# 12.net
KiCad netlist of a schematic drawn in Altium Designer
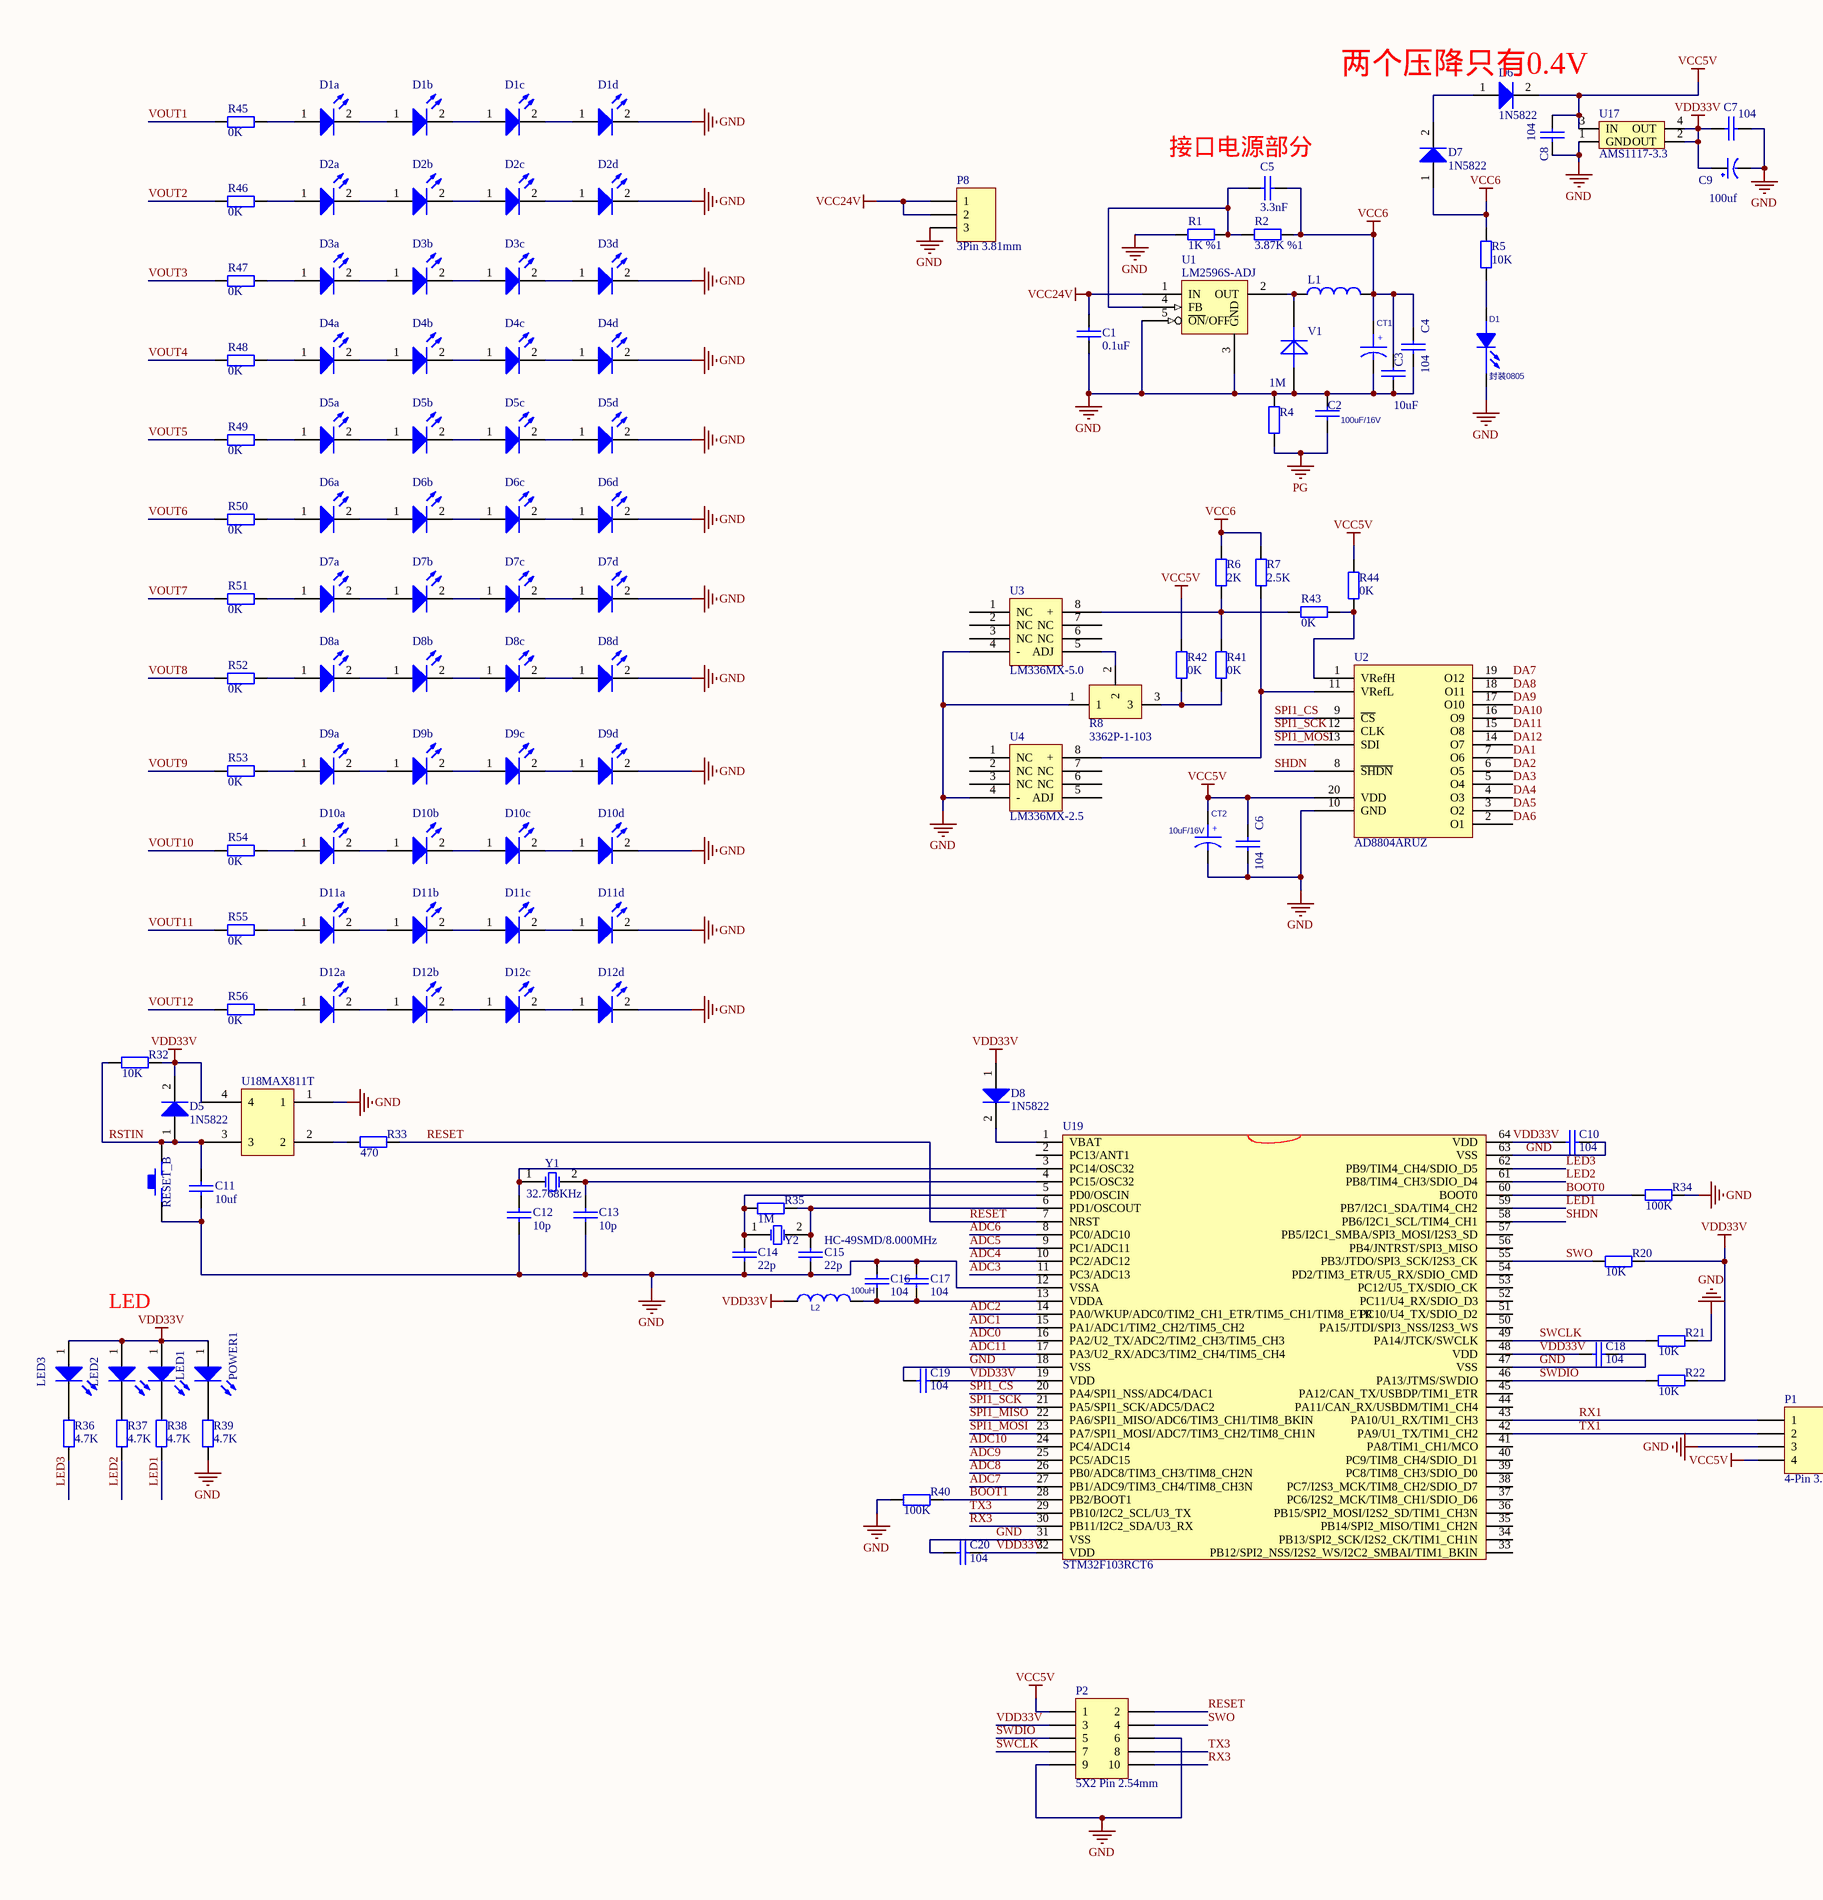
[diagram p0: 数粒机发射板12通道.SchDoc, left]
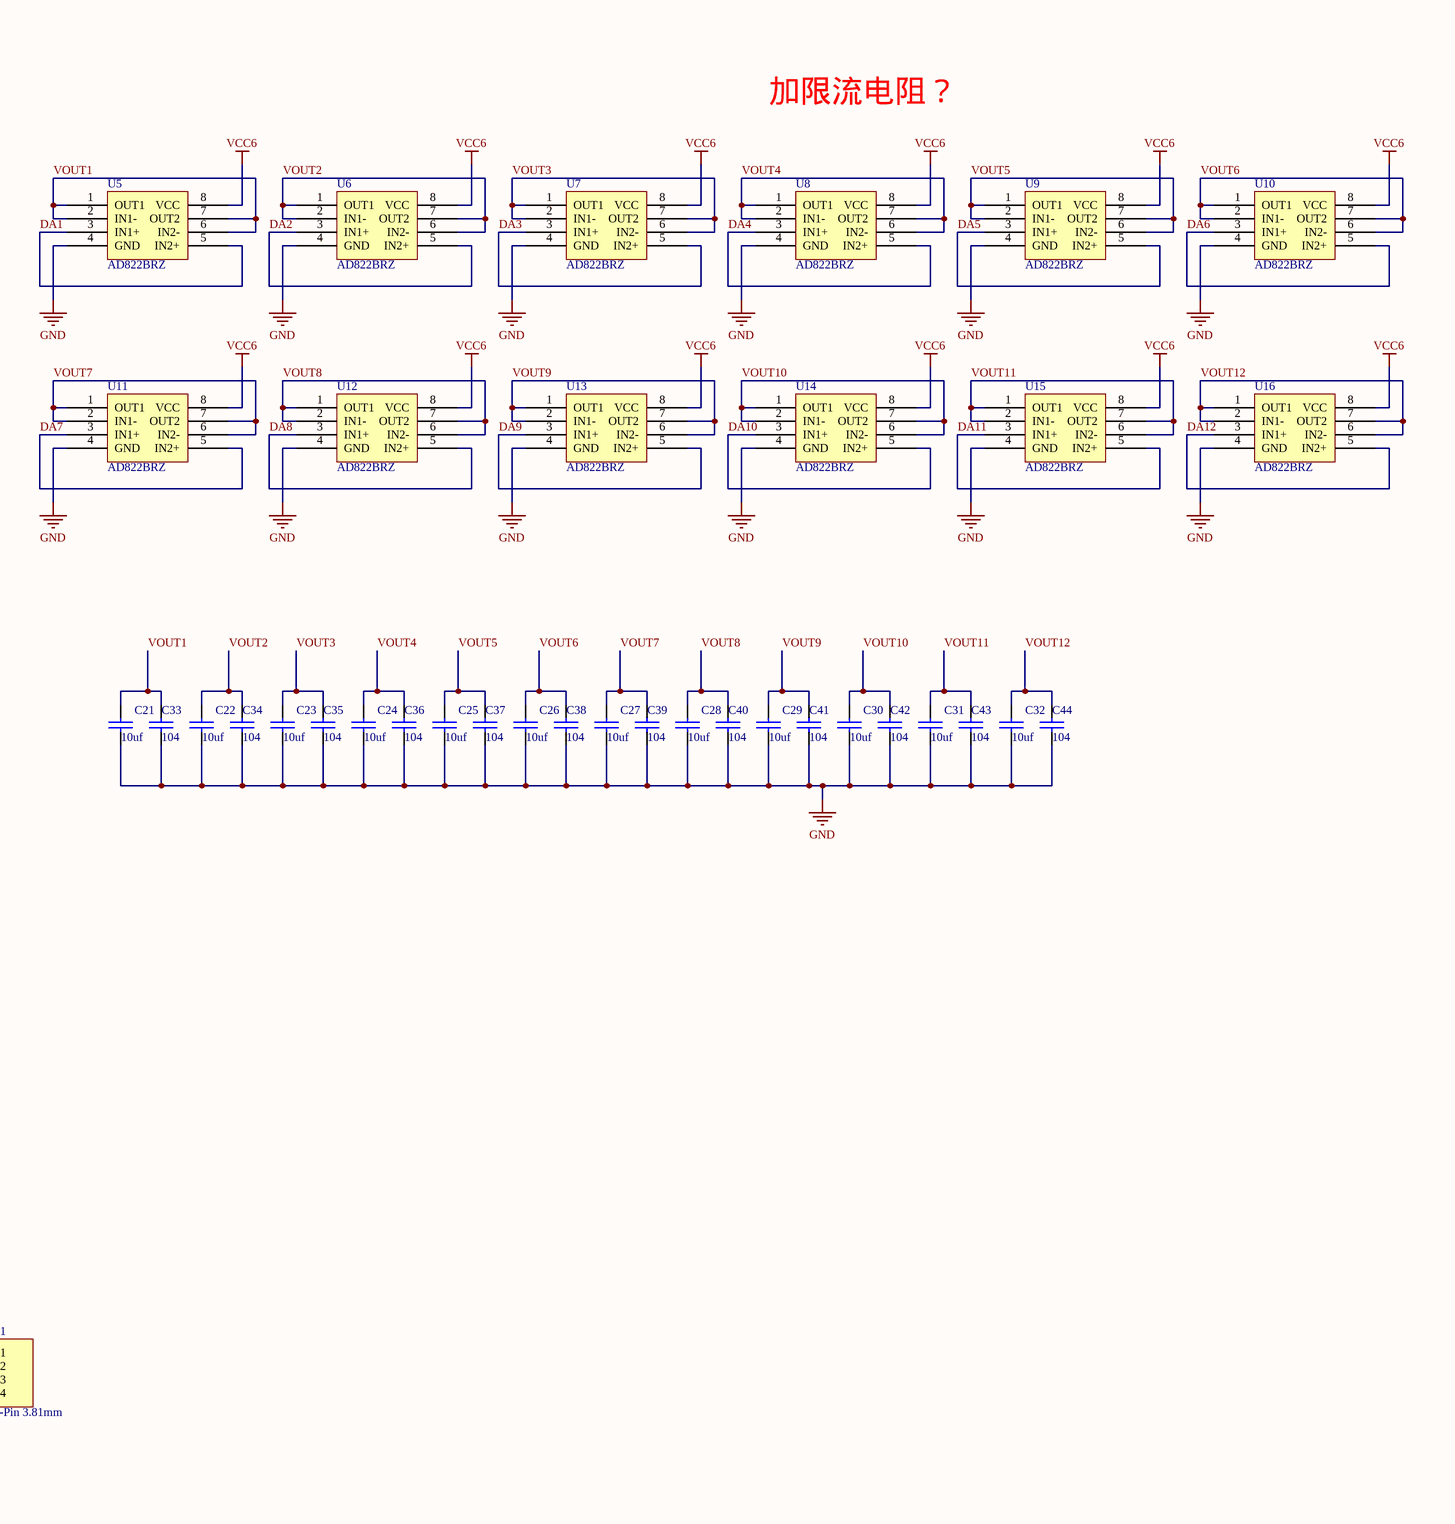
[diagram p1: 数粒机发射板12通道.SchDoc, right]

(export (version "E")
  (design (tool "Eeschema 10.0.6"))
  (components
    (comp (ref "C1")
      (value "0.1uF")
      (footprint "0805C")
      (description "贴片电容")
      (libsource (lib "*") (part "Pro92D1.TMP_105_9"))
    )
    (comp (ref "C2")
      (value "102/2KV")
      (footprint "0805CC")
      (description "贴片电容")
      (libsource (lib "*") (part "CAP"))
    )
    (comp (ref "C3")
      (value "10uF")
      (footprint "0805C")
      (description "贴片电容")
      (libsource (lib "*") (part "Pro92D1.TMP_105_9"))
    )
    (comp (ref "C4")
      (value "104")
      (footprint "0805C")
      (description "贴片电容")
      (libsource (lib "*") (part "CAP"))
    )
    (comp (ref "C5")
      (value "3.3nF")
      (footprint "0805C")
      (description "贴片电容")
      (libsource (lib "*") (part "CAP"))
    )
    (comp (ref "C6")
      (value "104")
      (footprint "0805C")
      (description "贴片电容")
      (libsource (lib "*") (part "CAP"))
    )
    (comp (ref "C7")
      (value "104")
      (footprint "0805C")
      (description "贴片电容")
      (libsource (lib "*") (part "CAP"))
    )
    (comp (ref "C8")
      (value "104")
      (footprint "0805C")
      (description "贴片电容")
      (libsource (lib "*") (part "CAP"))
    )
    (comp (ref "C9")
      (value "100uf")
      (footprint "CC6.56.5")
      (description "贴片电解电容")
      (fields (field (name "Comment") "10SEV100M6.3X5.5"))
      (libsource (lib "WarShip V3 STM32103封装库") (part "CAP"))
    )
    (comp (ref "C10")
      (value "104")
      (footprint "0805C")
      (description "贴片电容")
      (libsource (lib "*") (part "CAP"))
    )
    (comp (ref "C11")
      (value "10uf")
      (footprint "0805C")
      (description "贴片电容")
      (libsource (lib "*") (part "CAP"))
    )
    (comp (ref "C12")
      (value "10p")
      (footprint "0805C")
      (description "贴片电容")
      (libsource (lib "*") (part "CAP"))
    )
    (comp (ref "C13")
      (value "10p")
      (footprint "0805C")
      (description "贴片电容")
      (libsource (lib "*") (part "CAP"))
    )
    (comp (ref "C14")
      (value "22p")
      (footprint "0805C")
      (description "贴片电容")
      (libsource (lib "*") (part "CAP"))
    )
    (comp (ref "C15")
      (value "22p")
      (footprint "0805C")
      (description "贴片电容")
      (libsource (lib "*") (part "CAP"))
    )
    (comp (ref "C16")
      (value "104")
      (footprint "0805C")
      (description "贴片电容")
      (libsource (lib "*") (part "CAP"))
    )
    (comp (ref "C17")
      (value "104")
      (footprint "0805C")
      (description "贴片电容")
      (libsource (lib "*") (part "CAP"))
    )
    (comp (ref "C18")
      (value "104")
      (footprint "0805C")
      (description "贴片电容")
      (libsource (lib "*") (part "CAP"))
    )
    (comp (ref "C19")
      (value "104")
      (footprint "0805C")
      (description "贴片电容")
      (libsource (lib "*") (part "CAP"))
    )
    (comp (ref "C20")
      (value "104")
      (footprint "0805C")
      (description "贴片电容")
      (libsource (lib "*") (part "CAP"))
    )
    (comp (ref "C21")
      (value "10uf")
      (footprint "0805C")
      (description "贴片电容")
      (libsource (lib "*") (part "CAP"))
    )
    (comp (ref "C22")
      (value "10uf")
      (footprint "0805C")
      (description "贴片电容")
      (libsource (lib "*") (part "CAP"))
    )
    (comp (ref "C23")
      (value "10uf")
      (footprint "0805C")
      (description "贴片电容")
      (libsource (lib "*") (part "CAP"))
    )
    (comp (ref "C24")
      (value "10uf")
      (footprint "0805C")
      (description "贴片电容")
      (libsource (lib "*") (part "CAP"))
    )
    (comp (ref "C25")
      (value "10uf")
      (footprint "0805C")
      (description "贴片电容")
      (libsource (lib "*") (part "CAP"))
    )
    (comp (ref "C26")
      (value "10uf")
      (footprint "0805C")
      (description "贴片电容")
      (libsource (lib "*") (part "CAP"))
    )
    (comp (ref "C27")
      (value "10uf")
      (footprint "0805C")
      (description "贴片电容")
      (libsource (lib "*") (part "CAP"))
    )
    (comp (ref "C28")
      (value "10uf")
      (footprint "0805C")
      (description "贴片电容")
      (libsource (lib "*") (part "CAP"))
    )
    (comp (ref "C29")
      (value "10uf")
      (footprint "0805C")
      (description "贴片电容")
      (libsource (lib "*") (part "CAP"))
    )
    (comp (ref "C30")
      (value "10uf")
      (footprint "0805C")
      (description "贴片电容")
      (libsource (lib "*") (part "CAP"))
    )
    (comp (ref "C31")
      (value "10uf")
      (footprint "0805C")
      (description "贴片电容")
      (libsource (lib "*") (part "CAP"))
    )
    (comp (ref "C32")
      (value "10uf")
      (footprint "0805C")
      (description "贴片电容")
      (libsource (lib "*") (part "CAP"))
    )
    (comp (ref "C33")
      (value "104")
      (footprint "0805C")
      (description "贴片电容")
      (libsource (lib "*") (part "CAP"))
    )
    (comp (ref "C34")
      (value "104")
      (footprint "0805C")
      (description "贴片电容")
      (libsource (lib "*") (part "CAP"))
    )
    (comp (ref "C35")
      (value "104")
      (footprint "0805C")
      (description "贴片电容")
      (libsource (lib "*") (part "CAP"))
    )
    (comp (ref "C36")
      (value "104")
      (footprint "0805C")
      (description "贴片电容")
      (libsource (lib "*") (part "CAP"))
    )
    (comp (ref "C37")
      (value "104")
      (footprint "0805C")
      (description "贴片电容")
      (libsource (lib "*") (part "CAP"))
    )
    (comp (ref "C38")
      (value "104")
      (footprint "0805C")
      (description "贴片电容")
      (libsource (lib "*") (part "CAP"))
    )
    (comp (ref "C39")
      (value "104")
      (footprint "0805C")
      (description "贴片电容")
      (libsource (lib "*") (part "CAP"))
    )
    (comp (ref "C40")
      (value "104")
      (footprint "0805C")
      (description "贴片电容")
      (libsource (lib "*") (part "CAP"))
    )
    (comp (ref "C41")
      (value "104")
      (footprint "0805C")
      (description "贴片电容")
      (libsource (lib "*") (part "CAP"))
    )
    (comp (ref "C42")
      (value "104")
      (footprint "0805C")
      (description "贴片电容")
      (libsource (lib "*") (part "CAP"))
    )
    (comp (ref "C43")
      (value "104")
      (footprint "0805C")
      (description "贴片电容")
      (libsource (lib "*") (part "CAP"))
    )
    (comp (ref "C44")
      (value "104")
      (footprint "0805C")
      (description "贴片电容")
      (libsource (lib "*") (part "CAP"))
    )
    (comp (ref "CT1")
      (value "100uF/16V")
      (description "钽电容")
      (fields (field (name "VENDOR PART#") "495-2256-1-ND") (field (name "MFG PART#") "B45196H3107M409"))
      (libsource (lib "*") (part "CAP POL"))
    )
    (comp (ref "CT2")
      (value "10uF/16V")
      (description "钽电容")
      (fields (field (name "VENDOR PART#") "495-2256-1-ND") (field (name "MFG PART#") "B45196H3107M409"))
      (libsource (lib "*") (part "CAP POL"))
    )
    (comp (ref "D1")
      (value "封装0805")
      (description "二极管(贴片发光红色)")
      (fields (field (name "VENDOR PART#") "160-1426-1-ND") (field (name "MFG PART#") "LTST-C171KGKT"))
      (libsource (lib "*") (part "LED"))
    )
    (comp (ref "D1a")
      (value "EL-1KL3")
      (footprint "EL-1KL3")
      (description "红外接收珠子")
      (fields (field (name "PUBLISHER") "Altium Limited"))
      (libsource (lib "Miscellaneous Devices") (part "EL-1KL3"))
    )
    (comp (ref "D1b")
      (value "EL-1KL3")
      (footprint "EL-1KL3")
      (description "红外接收珠子")
      (fields (field (name "PUBLISHER") "Altium Limited"))
      (libsource (lib "Miscellaneous Devices") (part "EL-1KL3"))
    )
    (comp (ref "D1c")
      (value "EL-1KL3")
      (footprint "EL-1KL3")
      (description "红外接收珠子")
      (fields (field (name "PUBLISHER") "Altium Limited"))
      (libsource (lib "Miscellaneous Devices") (part "EL-1KL3"))
    )
    (comp (ref "D1d")
      (value "EL-1KL3")
      (footprint "EL-1KL3")
      (description "红外接收珠子")
      (fields (field (name "PUBLISHER") "Altium Limited"))
      (libsource (lib "Miscellaneous Devices") (part "EL-1KL3"))
    )
    (comp (ref "D2a")
      (value "EL-1KL3")
      (footprint "EL-1KL3")
      (description "红外接收珠子")
      (fields (field (name "PUBLISHER") "Altium Limited"))
      (libsource (lib "Miscellaneous Devices") (part "EL-1KL3"))
    )
    (comp (ref "D2b")
      (value "EL-1KL3")
      (footprint "EL-1KL3")
      (description "红外接收珠子")
      (fields (field (name "PUBLISHER") "Altium Limited"))
      (libsource (lib "Miscellaneous Devices") (part "EL-1KL3"))
    )
    (comp (ref "D2c")
      (value "EL-1KL3")
      (footprint "EL-1KL3")
      (description "红外接收珠子")
      (fields (field (name "PUBLISHER") "Altium Limited"))
      (libsource (lib "Miscellaneous Devices") (part "EL-1KL3"))
    )
    (comp (ref "D2d")
      (value "EL-1KL3")
      (footprint "EL-1KL3")
      (description "红外接收珠子")
      (fields (field (name "PUBLISHER") "Altium Limited"))
      (libsource (lib "Miscellaneous Devices") (part "EL-1KL3"))
    )
    (comp (ref "D3a")
      (value "EL-1KL3")
      (footprint "EL-1KL3")
      (description "红外接收珠子")
      (fields (field (name "PUBLISHER") "Altium Limited"))
      (libsource (lib "Miscellaneous Devices") (part "EL-1KL3"))
    )
    (comp (ref "D3b")
      (value "EL-1KL3")
      (footprint "EL-1KL3")
      (description "红外接收珠子")
      (fields (field (name "PUBLISHER") "Altium Limited"))
      (libsource (lib "Miscellaneous Devices") (part "EL-1KL3"))
    )
    (comp (ref "D3c")
      (value "EL-1KL3")
      (footprint "EL-1KL3")
      (description "红外接收珠子")
      (fields (field (name "PUBLISHER") "Altium Limited"))
      (libsource (lib "Miscellaneous Devices") (part "EL-1KL3"))
    )
    (comp (ref "D3d")
      (value "EL-1KL3")
      (footprint "EL-1KL3")
      (description "红外接收珠子")
      (fields (field (name "PUBLISHER") "Altium Limited"))
      (libsource (lib "Miscellaneous Devices") (part "EL-1KL3"))
    )
    (comp (ref "D4a")
      (value "EL-1KL3")
      (footprint "EL-1KL3")
      (description "红外接收珠子")
      (fields (field (name "PUBLISHER") "Altium Limited"))
      (libsource (lib "Miscellaneous Devices") (part "EL-1KL3"))
    )
    (comp (ref "D4b")
      (value "EL-1KL3")
      (footprint "EL-1KL3")
      (description "红外接收珠子")
      (fields (field (name "PUBLISHER") "Altium Limited"))
      (libsource (lib "Miscellaneous Devices") (part "EL-1KL3"))
    )
    (comp (ref "D4c")
      (value "EL-1KL3")
      (footprint "EL-1KL3")
      (description "红外接收珠子")
      (fields (field (name "PUBLISHER") "Altium Limited"))
      (libsource (lib "Miscellaneous Devices") (part "EL-1KL3"))
    )
    (comp (ref "D4d")
      (value "EL-1KL3")
      (footprint "EL-1KL3")
      (description "红外接收珠子")
      (fields (field (name "PUBLISHER") "Altium Limited"))
      (libsource (lib "Miscellaneous Devices") (part "EL-1KL3"))
    )
    (comp (ref "D5")
      (value "1N5822")
      (footprint "D1206")
      (description "二极管(贴片)")
      (fields (field (name "Comment") "1N5822/1206"))
      (libsource (lib "altium-import") (part "root_1_DIODE 1N4148/1206_"))
    )
    (comp (ref "D5a")
      (value "EL-1KL3")
      (footprint "EL-1KL3")
      (description "红外接收珠子")
      (fields (field (name "PUBLISHER") "Altium Limited"))
      (libsource (lib "Miscellaneous Devices") (part "EL-1KL3"))
    )
    (comp (ref "D5b")
      (value "EL-1KL3")
      (footprint "EL-1KL3")
      (description "红外接收珠子")
      (fields (field (name "PUBLISHER") "Altium Limited"))
      (libsource (lib "Miscellaneous Devices") (part "EL-1KL3"))
    )
    (comp (ref "D5c")
      (value "EL-1KL3")
      (footprint "EL-1KL3")
      (description "红外接收珠子")
      (fields (field (name "PUBLISHER") "Altium Limited"))
      (libsource (lib "Miscellaneous Devices") (part "EL-1KL3"))
    )
    (comp (ref "D5d")
      (value "EL-1KL3")
      (footprint "EL-1KL3")
      (description "红外接收珠子")
      (fields (field (name "PUBLISHER") "Altium Limited"))
      (libsource (lib "Miscellaneous Devices") (part "EL-1KL3"))
    )
    (comp (ref "D6")
      (value "1N5822")
      (footprint "D1206")
      (description "二极管(贴片)")
      (fields (field (name "Comment") "1N5822/1206"))
      (libsource (lib "altium-import") (part "root_0_DIODE 1N4148/1206_"))
    )
    (comp (ref "D6a")
      (value "EL-1KL3")
      (footprint "EL-1KL3")
      (description "红外接收珠子")
      (fields (field (name "PUBLISHER") "Altium Limited"))
      (libsource (lib "Miscellaneous Devices") (part "EL-1KL3"))
    )
    (comp (ref "D6b")
      (value "EL-1KL3")
      (footprint "EL-1KL3")
      (description "红外接收珠子")
      (fields (field (name "PUBLISHER") "Altium Limited"))
      (libsource (lib "Miscellaneous Devices") (part "EL-1KL3"))
    )
    (comp (ref "D6c")
      (value "EL-1KL3")
      (footprint "EL-1KL3")
      (description "红外接收珠子")
      (fields (field (name "PUBLISHER") "Altium Limited"))
      (libsource (lib "Miscellaneous Devices") (part "EL-1KL3"))
    )
    (comp (ref "D6d")
      (value "EL-1KL3")
      (footprint "EL-1KL3")
      (description "红外接收珠子")
      (fields (field (name "PUBLISHER") "Altium Limited"))
      (libsource (lib "Miscellaneous Devices") (part "EL-1KL3"))
    )
    (comp (ref "D7")
      (value "1N5822")
      (footprint "D1206")
      (description "二极管(贴片)")
      (fields (field (name "Comment") "1N5822/1206"))
      (libsource (lib "altium-import") (part "root_1_DIODE 1N4148/1206_"))
    )
    (comp (ref "D7a")
      (value "EL-1KL3")
      (footprint "EL-1KL3")
      (description "红外接收珠子")
      (fields (field (name "PUBLISHER") "Altium Limited"))
      (libsource (lib "Miscellaneous Devices") (part "EL-1KL3"))
    )
    (comp (ref "D7b")
      (value "EL-1KL3")
      (footprint "EL-1KL3")
      (description "红外接收珠子")
      (fields (field (name "PUBLISHER") "Altium Limited"))
      (libsource (lib "Miscellaneous Devices") (part "EL-1KL3"))
    )
    (comp (ref "D7c")
      (value "EL-1KL3")
      (footprint "EL-1KL3")
      (description "红外接收珠子")
      (fields (field (name "PUBLISHER") "Altium Limited"))
      (libsource (lib "Miscellaneous Devices") (part "EL-1KL3"))
    )
    (comp (ref "D7d")
      (value "EL-1KL3")
      (footprint "EL-1KL3")
      (description "红外接收珠子")
      (fields (field (name "PUBLISHER") "Altium Limited"))
      (libsource (lib "Miscellaneous Devices") (part "EL-1KL3"))
    )
    (comp (ref "D8")
      (value "1N5822")
      (footprint "D1206")
      (description "二极管(贴片)")
      (fields (field (name "Comment") "1N5822/1206"))
      (libsource (lib "altium-import") (part "root_3_DIODE 1N4148/1206_"))
    )
    (comp (ref "D8a")
      (value "EL-1KL3")
      (footprint "EL-1KL3")
      (description "红外接收珠子")
      (fields (field (name "PUBLISHER") "Altium Limited"))
      (libsource (lib "Miscellaneous Devices") (part "EL-1KL3"))
    )
    (comp (ref "D8b")
      (value "EL-1KL3")
      (footprint "EL-1KL3")
      (description "红外接收珠子")
      (fields (field (name "PUBLISHER") "Altium Limited"))
      (libsource (lib "Miscellaneous Devices") (part "EL-1KL3"))
    )
    (comp (ref "D8c")
      (value "EL-1KL3")
      (footprint "EL-1KL3")
      (description "红外接收珠子")
      (fields (field (name "PUBLISHER") "Altium Limited"))
      (libsource (lib "Miscellaneous Devices") (part "EL-1KL3"))
    )
    (comp (ref "D8d")
      (value "EL-1KL3")
      (footprint "EL-1KL3")
      (description "红外接收珠子")
      (fields (field (name "PUBLISHER") "Altium Limited"))
      (libsource (lib "Miscellaneous Devices") (part "EL-1KL3"))
    )
    (comp (ref "D9a")
      (value "EL-1KL3")
      (footprint "EL-1KL3")
      (description "红外接收珠子")
      (fields (field (name "PUBLISHER") "Altium Limited"))
      (libsource (lib "Miscellaneous Devices") (part "EL-1KL3"))
    )
    (comp (ref "D9b")
      (value "EL-1KL3")
      (footprint "EL-1KL3")
      (description "红外接收珠子")
      (fields (field (name "PUBLISHER") "Altium Limited"))
      (libsource (lib "Miscellaneous Devices") (part "EL-1KL3"))
    )
    (comp (ref "D9c")
      (value "EL-1KL3")
      (footprint "EL-1KL3")
      (description "红外接收珠子")
      (fields (field (name "PUBLISHER") "Altium Limited"))
      (libsource (lib "Miscellaneous Devices") (part "EL-1KL3"))
    )
    (comp (ref "D9d")
      (value "EL-1KL3")
      (footprint "EL-1KL3")
      (description "红外接收珠子")
      (fields (field (name "PUBLISHER") "Altium Limited"))
      (libsource (lib "Miscellaneous Devices") (part "EL-1KL3"))
    )
    (comp (ref "D10a")
      (value "EL-1KL3")
      (footprint "EL-1KL3")
      (description "红外接收珠子")
      (fields (field (name "PUBLISHER") "Altium Limited"))
      (libsource (lib "Miscellaneous Devices") (part "EL-1KL3"))
    )
    (comp (ref "D10b")
      (value "EL-1KL3")
      (footprint "EL-1KL3")
      (description "红外接收珠子")
      (fields (field (name "PUBLISHER") "Altium Limited"))
      (libsource (lib "Miscellaneous Devices") (part "EL-1KL3"))
    )
    (comp (ref "D10c")
      (value "EL-1KL3")
      (footprint "EL-1KL3")
      (description "红外接收珠子")
      (fields (field (name "PUBLISHER") "Altium Limited"))
      (libsource (lib "Miscellaneous Devices") (part "EL-1KL3"))
    )
    (comp (ref "D10d")
      (value "EL-1KL3")
      (footprint "EL-1KL3")
      (description "红外接收珠子")
      (fields (field (name "PUBLISHER") "Altium Limited"))
      (libsource (lib "Miscellaneous Devices") (part "EL-1KL3"))
    )
    (comp (ref "D11a")
      (value "EL-1KL3")
      (footprint "EL-1KL3")
      (description "红外接收珠子")
      (fields (field (name "PUBLISHER") "Altium Limited"))
      (libsource (lib "Miscellaneous Devices") (part "EL-1KL3"))
    )
    (comp (ref "D11b")
      (value "EL-1KL3")
      (footprint "EL-1KL3")
      (description "红外接收珠子")
      (fields (field (name "PUBLISHER") "Altium Limited"))
      (libsource (lib "Miscellaneous Devices") (part "EL-1KL3"))
    )
    (comp (ref "D11c")
      (value "EL-1KL3")
      (footprint "EL-1KL3")
      (description "红外接收珠子")
      (fields (field (name "PUBLISHER") "Altium Limited"))
      (libsource (lib "Miscellaneous Devices") (part "EL-1KL3"))
    )
    (comp (ref "D11d")
      (value "EL-1KL3")
      (footprint "EL-1KL3")
      (description "红外接收珠子")
      (fields (field (name "PUBLISHER") "Altium Limited"))
      (libsource (lib "Miscellaneous Devices") (part "EL-1KL3"))
    )
    (comp (ref "D12a")
      (value "EL-1KL3")
      (footprint "EL-1KL3")
      (description "红外接收珠子")
      (fields (field (name "PUBLISHER") "Altium Limited"))
      (libsource (lib "Miscellaneous Devices") (part "EL-1KL3"))
    )
    (comp (ref "D12b")
      (value "EL-1KL3")
      (footprint "EL-1KL3")
      (description "红外接收珠子")
      (fields (field (name "PUBLISHER") "Altium Limited"))
      (libsource (lib "Miscellaneous Devices") (part "EL-1KL3"))
    )
    (comp (ref "D12c")
      (value "EL-1KL3")
      (footprint "EL-1KL3")
      (description "红外接收珠子")
      (fields (field (name "PUBLISHER") "Altium Limited"))
      (libsource (lib "Miscellaneous Devices") (part "EL-1KL3"))
    )
    (comp (ref "D12d")
      (value "EL-1KL3")
      (footprint "EL-1KL3")
      (description "红外接收珠子")
      (fields (field (name "PUBLISHER") "Altium Limited"))
      (libsource (lib "Miscellaneous Devices") (part "EL-1KL3"))
    )
    (comp (ref "L1")
      (value "33uH2A")
      (footprint "6045")
      (description "贴片电感")
      (fields (field (name "PUBLISHER") "Altium Limited"))
      (libsource (lib "Miscellaneous Devices") (part "Inductor"))
    )
    (comp (ref "L2")
      (value "100uH")
      (description "贴片电感")
      (fields (field (name "MFG") "Murata") (field (name "MFG PART#") "BLM18PG121SN1D"))
      (libsource (lib "*") (part "FERRITE"))
    )
    (comp (ref "LED1")
      (value "封装0805")
      (footprint "LED-0805")
      (description "二极管(贴片发光绿色)")
      (libsource (lib "SCH_XIJUN") (part "LED_GREEN 0805"))
    )
    (comp (ref "LED2")
      (value "封装0805")
      (footprint "LED-0805")
      (description "二极管(贴片发光绿色)")
      (libsource (lib "SCH_XIJUN") (part "LED_GREEN 0805"))
    )
    (comp (ref "LED3")
      (value "封装0805")
      (footprint "LED-0805")
      (description "二极管(贴片发光绿色)")
      (libsource (lib "SCH_XIJUN") (part "LED_GREEN 0805"))
    )
    (comp (ref "P1")
      (value "4-Pin 3.81mm")
      (footprint "con4")
      (description "绿色PCB插座(配插头)")
      (fields (field (name "PUBLISHER") "Altium Limited"))
      (libsource (lib "Miscellaneous Connectors") (part "Header 4"))
    )
    (comp (ref "P2")
      (value "5X2 Pin 2.54mm")
      (footprint "idc-10-b")
      (description "JTAG简易牛角插")
      (fields (field (name "PUBLISHER") "Altium Limited"))
      (libsource (lib "Miscellaneous Connectors") (part "Header 5X2"))
    )
    (comp (ref "P8")
      (value "3Pin 3.81mm")
      (footprint "CON3")
      (description "绿色PCB插座(配插头)")
      (fields (field (name "PUBLISHER") "Altium Limited"))
      (libsource (lib "Miscellaneous Connectors") (part "Header 3"))
    )
    (comp (ref "POWER1")
      (value "封装0805")
      (footprint "LED-0805")
      (description "二极管(贴片发光红色)")
      (libsource (lib "SCH_XIJUN") (part "LED_GREEN 0805"))
    )
    (comp (ref "R1")
      (value "1K %1")
      (footprint "0805R")
      (description "贴片电阻")
      (fields (field (name "PUBLISHER") "Altium Limited"))
      (libsource (lib "") (part "Res2_1"))
    )
    (comp (ref "R2")
      (value "3.87K %1")
      (footprint "0805R")
      (description "贴片电阻")
      (fields (field (name "PUBLISHER") "Altium Limited"))
      (libsource (lib "") (part "Res2_1"))
    )
    (comp (ref "R4")
      (value "1M")
      (footprint "0805R")
      (description "贴片电阻")
      (fields (field (name "PUBLISHER") "Altium Limited"))
      (libsource (lib "") (part "Res2_2"))
    )
    (comp (ref "R5")
      (value "10K")
      (footprint "0805R")
      (description "贴片电阻")
      (fields (field (name "PUBLISHER") "Altium Limited"))
      (libsource (lib "Miscellaneous Devices") (part "Res2"))
    )
    (comp (ref "R6")
      (value "2K")
      (footprint "0805R")
      (description "贴片电阻")
      (fields (field (name "PUBLISHER") "Altium Limited"))
      (libsource (lib "Miscellaneous Devices") (part "Res2"))
    )
    (comp (ref "R7")
      (value "2.5K")
      (footprint "0805R")
      (description "贴片电阻")
      (fields (field (name "PUBLISHER") "Altium Limited"))
      (libsource (lib "Miscellaneous Devices") (part "Res2"))
    )
    (comp (ref "R8")
      (value "3362P-1-103")
      (footprint "VR4")
      (description "电位器 10K")
      (libsource (lib "MYlib") (part "3362P"))
    )
    (comp (ref "R20")
      (value "10K")
      (footprint "0805R")
      (description "贴片电阻")
      (fields (field (name "PUBLISHER") "Altium Limited"))
      (libsource (lib "") (part "Res2_1"))
    )
    (comp (ref "R21")
      (value "10K")
      (footprint "0805R")
      (description "贴片电阻")
      (fields (field (name "PUBLISHER") "Altium Limited"))
      (libsource (lib "") (part "Res2_1"))
    )
    (comp (ref "R22")
      (value "10K")
      (footprint "0805R")
      (description "贴片电阻")
      (fields (field (name "PUBLISHER") "Altium Limited"))
      (libsource (lib "") (part "Res2_1"))
    )
    (comp (ref "R32")
      (value "10K")
      (footprint "0805R")
      (description "贴片电阻")
      (fields (field (name "Comment") "1M") (field (name "PUBLISHER") "Altium Limited"))
      (libsource (lib "") (part "Res2_1"))
    )
    (comp (ref "R33")
      (value "470")
      (footprint "0805R")
      (description "贴片电阻")
      (fields (field (name "Comment") "1M") (field (name "PUBLISHER") "Altium Limited"))
      (libsource (lib "") (part "Res2_1"))
    )
    (comp (ref "R34")
      (value "100K")
      (footprint "0805R")
      (description "贴片电阻")
      (fields (field (name "PUBLISHER") "Altium Limited"))
      (libsource (lib "") (part "Res2_1"))
    )
    (comp (ref "R35")
      (value "1M")
      (footprint "0805R")
      (description "贴片电阻")
      (fields (field (name "PUBLISHER") "Altium Limited"))
      (libsource (lib "") (part "Res2_1"))
    )
    (comp (ref "R36")
      (value "4.7K")
      (footprint "0805R")
      (description "贴片电阻")
      (fields (field (name "Comment") "1M") (field (name "PUBLISHER") "Altium Limited"))
      (libsource (lib "My Library") (part "Res2"))
    )
    (comp (ref "R37")
      (value "4.7K")
      (footprint "0805R")
      (description "贴片电阻")
      (fields (field (name "Comment") "1M") (field (name "PUBLISHER") "Altium Limited"))
      (libsource (lib "My Library") (part "Res2"))
    )
    (comp (ref "R38")
      (value "4.7K")
      (footprint "0805R")
      (description "贴片电阻")
      (fields (field (name "Comment") "1M") (field (name "PUBLISHER") "Altium Limited"))
      (libsource (lib "My Library") (part "Res2"))
    )
    (comp (ref "R39")
      (value "4.7K")
      (footprint "0805R")
      (description "贴片电阻")
      (fields (field (name "Comment") "1M") (field (name "PUBLISHER") "Altium Limited"))
      (libsource (lib "My Library") (part "Res2"))
    )
    (comp (ref "R40")
      (value "100K")
      (footprint "0805R")
      (description "贴片电阻")
      (fields (field (name "PUBLISHER") "Altium Limited"))
      (libsource (lib "") (part "Res2_1"))
    )
    (comp (ref "R41")
      (value "0K")
      (footprint "0805R")
      (description "贴片电阻")
      (fields (field (name "PUBLISHER") "Altium Limited"))
      (libsource (lib "Miscellaneous Devices") (part "Res2"))
    )
    (comp (ref "R42")
      (value "0K")
      (footprint "0805R")
      (description "贴片电阻")
      (fields (field (name "PUBLISHER") "Altium Limited"))
      (libsource (lib "Miscellaneous Devices") (part "Res2"))
    )
    (comp (ref "R43")
      (value "0K")
      (footprint "0805R")
      (description "贴片电阻")
      (fields (field (name "PUBLISHER") "Altium Limited"))
      (libsource (lib "") (part "Res2_1"))
    )
    (comp (ref "R44")
      (value "0K")
      (footprint "0805R")
      (description "贴片电阻")
      (fields (field (name "PUBLISHER") "Altium Limited"))
      (libsource (lib "Miscellaneous Devices") (part "Res2"))
    )
    (comp (ref "R45")
      (value "0K")
      (footprint "0805R")
      (description "贴片电阻")
      (fields (field (name "PUBLISHER") "Altium Limited"))
      (libsource (lib "") (part "Res2_2"))
    )
    (comp (ref "R46")
      (value "0K")
      (footprint "0805R")
      (description "贴片电阻")
      (fields (field (name "PUBLISHER") "Altium Limited"))
      (libsource (lib "") (part "Res2_2"))
    )
    (comp (ref "R47")
      (value "0K")
      (footprint "0805R")
      (description "贴片电阻")
      (fields (field (name "PUBLISHER") "Altium Limited"))
      (libsource (lib "") (part "Res2_2"))
    )
    (comp (ref "R48")
      (value "0K")
      (footprint "0805R")
      (description "贴片电阻")
      (fields (field (name "PUBLISHER") "Altium Limited"))
      (libsource (lib "") (part "Res2_2"))
    )
    (comp (ref "R49")
      (value "0K")
      (footprint "0805R")
      (description "贴片电阻")
      (fields (field (name "PUBLISHER") "Altium Limited"))
      (libsource (lib "") (part "Res2_2"))
    )
    (comp (ref "R50")
      (value "0K")
      (footprint "0805R")
      (description "贴片电阻")
      (fields (field (name "PUBLISHER") "Altium Limited"))
      (libsource (lib "") (part "Res2_2"))
    )
    (comp (ref "R51")
      (value "0K")
      (footprint "0805R")
      (description "贴片电阻")
      (fields (field (name "PUBLISHER") "Altium Limited"))
      (libsource (lib "") (part "Res2_2"))
    )
    (comp (ref "R52")
      (value "0K")
      (footprint "0805R")
      (description "贴片电阻")
      (fields (field (name "PUBLISHER") "Altium Limited"))
      (libsource (lib "") (part "Res2_2"))
    )
    (comp (ref "R53")
      (value "0K")
      (footprint "0805R")
      (description "贴片电阻")
      (fields (field (name "PUBLISHER") "Altium Limited"))
      (libsource (lib "") (part "Res2_2"))
    )
    (comp (ref "R54")
      (value "0K")
      (footprint "0805R")
      (description "贴片电阻")
      (fields (field (name "PUBLISHER") "Altium Limited"))
      (libsource (lib "") (part "Res2_2"))
    )
    (comp (ref "R55")
      (value "0K")
      (footprint "0805R")
      (description "贴片电阻")
      (fields (field (name "PUBLISHER") "Altium Limited"))
      (libsource (lib "") (part "Res2_2"))
    )
    (comp (ref "R56")
      (value "0K")
      (footprint "0805R")
      (description "贴片电阻")
      (fields (field (name "PUBLISHER") "Altium Limited"))
      (libsource (lib "") (part "Res2_2"))
    )
    (comp (ref "RESET_B")
      (value "3*6*2.5 白色按钮轻触开关 两脚 2P")
      (footprint "button_2")
      (description "贴片按键")
      (libsource (lib "WarShip V3 STM32103封装库") (part "KEY_M"))
    )
    (comp (ref "U1")
      (value "LM2596S-ADJ")
      (footprint "TO-263")
      (description "集成电路")
      (libsource (lib "*") (part "LM2575T5.0(5)"))
    )
    (comp (ref "U2")
      (value "AD8804ARUZ")
      (footprint "tssop20")
      (description "12通道 8位 DAC芯片 TSSOP20")
      (libsource (lib "MYlib") (part "AD8804"))
    )
    (comp (ref "U3")
      (value "LM336MX-5.0")
      (footprint "sop8")
      (description "基准电压 5V")
      (libsource (lib "MYlib") (part "LM335MX-5.0"))
    )
    (comp (ref "U4")
      (value "LM336MX-2.5")
      (footprint "sop8")
      (description "基准电压2.5V")
      (libsource (lib "MYlib") (part "LM335MX-5.0"))
    )
    (comp (ref "U5")
      (value "AD822BRZ")
      (footprint "sop8")
      (description "集成电路 运算放大器")
      (libsource (lib "MYlib") (part "AD822"))
    )
    (comp (ref "U6")
      (value "AD822BRZ")
      (footprint "sop8")
      (description "集成电路 运算放大器")
      (libsource (lib "MYlib") (part "AD822"))
    )
    (comp (ref "U7")
      (value "AD822BRZ")
      (footprint "sop8")
      (description "集成电路 运算放大器")
      (libsource (lib "MYlib") (part "AD822"))
    )
    (comp (ref "U8")
      (value "AD822BRZ")
      (footprint "sop8")
      (description "集成电路 运算放大器")
      (libsource (lib "MYlib") (part "AD822"))
    )
    (comp (ref "U9")
      (value "AD822BRZ")
      (footprint "sop8")
      (description "集成电路 运算放大器")
      (libsource (lib "MYlib") (part "AD822"))
    )
    (comp (ref "U10")
      (value "AD822BRZ")
      (footprint "sop8")
      (description "集成电路 运算放大器")
      (libsource (lib "MYlib") (part "AD822"))
    )
    (comp (ref "U11")
      (value "AD822BRZ")
      (footprint "sop8")
      (description "集成电路 运算放大器")
      (libsource (lib "MYlib") (part "AD822"))
    )
    (comp (ref "U12")
      (value "AD822BRZ")
      (footprint "sop8")
      (description "集成电路 运算放大器")
      (libsource (lib "MYlib") (part "AD822"))
    )
    (comp (ref "U13")
      (value "AD822BRZ")
      (footprint "sop8")
      (description "集成电路 运算放大器")
      (libsource (lib "MYlib") (part "AD822"))
    )
    (comp (ref "U14")
      (value "AD822BRZ")
      (footprint "sop8")
      (description "集成电路 运算放大器")
      (libsource (lib "MYlib") (part "AD822"))
    )
    (comp (ref "U15")
      (value "AD822BRZ")
      (footprint "sop8")
      (description "集成电路 运算放大器")
      (libsource (lib "MYlib") (part "AD822"))
    )
    (comp (ref "U16")
      (value "AD822BRZ")
      (footprint "sop8")
      (description "集成电路 运算放大器")
      (libsource (lib "MYlib") (part "AD822"))
    )
    (comp (ref "U17")
      (value "AMS1117-3.3")
      (footprint "AMS1117")
      (description "稳压芯片")
      (libsource (lib "WarShip V3 STM32103封装库") (part "AMS1117"))
    )
    (comp (ref "U18")
      (value "MAX811T")
      (footprint "MAX811T")
      (description "集成电路贴片")
      (fields (field (name "Comment") "MAX811T/SOT143"))
      (libsource (lib "altium-import") (part "root_0_Power MAX811T_"))
    )
    (comp (ref "U19")
      (value "STM32F103RCT6")
      (footprint "TQ64")
      (description "集成电路")
      (libsource (lib "MiniSTM32 V3.0封装库") (part "STM32F103RDT6"))
    )
    (comp (ref "V1")
      (value "SK210B")
      (footprint "1812DT")
      (description "二极管")
      (libsource (lib "SCH") (part "DIODE1"))
    )
    (comp (ref "Y1")
      (value "32.768KHz")
      (footprint "32.768khz")
      (description "晶体(直插)")
      (fields (field (name "Comment") "HC-49DIP/32.768KHz") (field (name "PUBLISHER") "Altium Limited"))
      (libsource (lib "altium-import") (part "root_0_CRYSTAL 12M HC-49SMD_"))
    )
    (comp (ref "Y2")
      (value "HC-49SMD/8.000MHz")
      (footprint "CRYSTAL_SMD")
      (description "晶体(贴片)")
      (fields (field (name "PUBLISHER") "Altium Limited"))
      (libsource (lib "altium-import") (part "root_0_CRYSTAL 12M HC-49SMD_"))
    )
  )
  (nets
    (net (code "1") (name "/ADC0") (class "Default")
      (node (ref "U19") (pin "16") (pinfunction "PA2/U2_TX/ADC2/TIM2_CH3/TIM5_CH3_16") (pintype "passive"))
    )
    (net (code "2") (name "/ADC1") (class "Default")
      (node (ref "U19") (pin "15") (pinfunction "PA1/ADC1/TIM2_CH2/TIM5_CH2_15") (pintype "passive"))
    )
    (net (code "3") (name "/ADC2") (class "Default")
      (node (ref "U19") (pin "14") (pinfunction "PA0/WKUP/ADC0/TIM2_CH1_ETR/TIM5_CH1/TIM8_ETR_14") (pintype "passive"))
    )
    (net (code "4") (name "/ADC3") (class "Default")
      (node (ref "U19") (pin "11") (pinfunction "PC3/ADC13_11") (pintype "passive"))
    )
    (net (code "5") (name "/ADC4") (class "Default")
      (node (ref "U19") (pin "10") (pinfunction "PC2/ADC12_10") (pintype "passive"))
    )
    (net (code "6") (name "/ADC5") (class "Default")
      (node (ref "U19") (pin "9") (pinfunction "PC1/ADC11_9") (pintype "passive"))
    )
    (net (code "7") (name "/ADC6") (class "Default")
      (node (ref "U19") (pin "8") (pinfunction "PC0/ADC10_8") (pintype "passive"))
    )
    (net (code "8") (name "/ADC7") (class "Default")
      (node (ref "U19") (pin "27") (pinfunction "PB1/ADC9/TIM3_CH4/TIM8_CH3N_27") (pintype "passive"))
    )
    (net (code "9") (name "/ADC8") (class "Default")
      (node (ref "U19") (pin "26") (pinfunction "PB0/ADC8/TIM3_CH3/TIM8_CH2N_26") (pintype "passive"))
    )
    (net (code "10") (name "/ADC9") (class "Default")
      (node (ref "U19") (pin "25") (pinfunction "PC5/ADC15_25") (pintype "passive"))
    )
    (net (code "11") (name "/ADC10") (class "Default")
      (node (ref "U19") (pin "24") (pinfunction "PC4/ADC14_24") (pintype "passive"))
    )
    (net (code "12") (name "/ADC11") (class "Default")
      (node (ref "U19") (pin "17") (pinfunction "PA3/U2_RX/ADC3/TIM2_CH4/TIM5_CH4_17") (pintype "passive"))
    )
    (net (code "13") (name "/BOOT0") (class "Default")
      (node (ref "R34") (pin "1") (pinfunction "1_1") (pintype "passive"))
      (node (ref "U19") (pin "60") (pinfunction "BOOT0_60") (pintype "passive"))
    )
    (net (code "14") (name "/BOOT1") (class "Default")
      (node (ref "R40") (pin "2") (pinfunction "2_2") (pintype "passive"))
      (node (ref "U19") (pin "28") (pinfunction "PB2/BOOT1_28") (pintype "passive"))
    )
    (net (code "15") (name "/DA1") (class "Default")
      (node (ref "U2") (pin "7") (pinfunction "O6_7") (pintype "passive"))
      (node (ref "U5") (pin "3") (pinfunction "IN1+_3") (pintype "passive"))
      (node (ref "U5") (pin "5") (pinfunction "IN2+_5") (pintype "passive"))
    )
    (net (code "16") (name "/DA2") (class "Default")
      (node (ref "U2") (pin "6") (pinfunction "O5_6") (pintype "passive"))
      (node (ref "U6") (pin "3") (pinfunction "IN1+_3") (pintype "passive"))
      (node (ref "U6") (pin "5") (pinfunction "IN2+_5") (pintype "passive"))
    )
    (net (code "17") (name "/DA3") (class "Default")
      (node (ref "U2") (pin "5") (pinfunction "O4_5") (pintype "passive"))
      (node (ref "U7") (pin "3") (pinfunction "IN1+_3") (pintype "passive"))
      (node (ref "U7") (pin "5") (pinfunction "IN2+_5") (pintype "passive"))
    )
    (net (code "18") (name "/DA4") (class "Default")
      (node (ref "U2") (pin "4") (pinfunction "O3_4") (pintype "passive"))
      (node (ref "U8") (pin "3") (pinfunction "IN1+_3") (pintype "passive"))
      (node (ref "U8") (pin "5") (pinfunction "IN2+_5") (pintype "passive"))
    )
    (net (code "19") (name "/DA5") (class "Default")
      (node (ref "U2") (pin "3") (pinfunction "O2_3") (pintype "passive"))
      (node (ref "U9") (pin "3") (pinfunction "IN1+_3") (pintype "passive"))
      (node (ref "U9") (pin "5") (pinfunction "IN2+_5") (pintype "passive"))
    )
    (net (code "20") (name "/DA6") (class "Default")
      (node (ref "U10") (pin "3") (pinfunction "IN1+_3") (pintype "passive"))
      (node (ref "U10") (pin "5") (pinfunction "IN2+_5") (pintype "passive"))
      (node (ref "U2") (pin "2") (pinfunction "O1_2") (pintype "passive"))
    )
    (net (code "21") (name "/DA7") (class "Default")
      (node (ref "U11") (pin "3") (pinfunction "IN1+_3") (pintype "passive"))
      (node (ref "U11") (pin "5") (pinfunction "IN2+_5") (pintype "passive"))
      (node (ref "U2") (pin "19") (pinfunction "O12_19") (pintype "passive"))
    )
    (net (code "22") (name "/DA8") (class "Default")
      (node (ref "U12") (pin "3") (pinfunction "IN1+_3") (pintype "passive"))
      (node (ref "U12") (pin "5") (pinfunction "IN2+_5") (pintype "passive"))
      (node (ref "U2") (pin "18") (pinfunction "O11_18") (pintype "passive"))
    )
    (net (code "23") (name "/DA9") (class "Default")
      (node (ref "U13") (pin "3") (pinfunction "IN1+_3") (pintype "passive"))
      (node (ref "U13") (pin "5") (pinfunction "IN2+_5") (pintype "passive"))
      (node (ref "U2") (pin "17") (pinfunction "O10_17") (pintype "passive"))
    )
    (net (code "24") (name "/DA10") (class "Default")
      (node (ref "U14") (pin "3") (pinfunction "IN1+_3") (pintype "passive"))
      (node (ref "U14") (pin "5") (pinfunction "IN2+_5") (pintype "passive"))
      (node (ref "U2") (pin "16") (pinfunction "O9_16") (pintype "passive"))
    )
    (net (code "25") (name "/DA11") (class "Default")
      (node (ref "U15") (pin "3") (pinfunction "IN1+_3") (pintype "passive"))
      (node (ref "U15") (pin "5") (pinfunction "IN2+_5") (pintype "passive"))
      (node (ref "U2") (pin "15") (pinfunction "O8_15") (pintype "passive"))
    )
    (net (code "26") (name "/DA12") (class "Default")
      (node (ref "U16") (pin "3") (pinfunction "IN1+_3") (pintype "passive"))
      (node (ref "U16") (pin "5") (pinfunction "IN2+_5") (pintype "passive"))
      (node (ref "U2") (pin "14") (pinfunction "O7_14") (pintype "passive"))
    )
    (net (code "27") (name "/LED1") (class "Default")
      (node (ref "R38") (pin "1") (pinfunction "1_1") (pintype "passive"))
      (node (ref "U19") (pin "59") (pinfunction "PB7/I2C1_SDA/TIM4_CH2_59") (pintype "passive"))
    )
    (net (code "28") (name "/LED2") (class "Default")
      (node (ref "R37") (pin "1") (pinfunction "1_1") (pintype "passive"))
      (node (ref "U19") (pin "61") (pinfunction "PB8/TIM4_CH3/SDIO_D4_61") (pintype "passive"))
    )
    (net (code "29") (name "/LED3") (class "Default")
      (node (ref "R36") (pin "1") (pinfunction "1_1") (pintype "passive"))
      (node (ref "U19") (pin "62") (pinfunction "PB9/TIM4_CH4/SDIO_D5_62") (pintype "passive"))
    )
    (net (code "30") (name "/RESET") (class "Default")
      (node (ref "P2") (pin "2") (pinfunction "2_2") (pintype "passive"))
      (node (ref "R33") (pin "2") (pinfunction "2_2") (pintype "passive"))
      (node (ref "U19") (pin "7") (pinfunction "NRST_7") (pintype "passive"))
    )
    (net (code "31") (name "/RSTIN") (class "Default")
      (node (ref "C11") (pin "2") (pinfunction "2_2") (pintype "passive"))
      (node (ref "D5") (pin "1") (pinfunction "A_1") (pintype "passive"))
      (node (ref "R32") (pin "1") (pinfunction "1_1") (pintype "passive"))
      (node (ref "RESET_B") (pin "2") (pinfunction "2_2") (pintype "passive"))
      (node (ref "U18") (pin "3") (pinfunction "3_3") (pintype "passive"))
    )
    (net (code "32") (name "/RX1") (class "Default")
      (node (ref "P1") (pin "1") (pinfunction "1_1") (pintype "passive"))
      (node (ref "U19") (pin "43") (pinfunction "PA10/U1_RX/TIM1_CH3_43") (pintype "passive"))
    )
    (net (code "33") (name "/RX3") (class "Default")
      (node (ref "P2") (pin "10") (pinfunction "10_10") (pintype "passive"))
      (node (ref "U19") (pin "30") (pinfunction "PB11/I2C2_SDA/U3_RX_30") (pintype "passive"))
    )
    (net (code "34") (name "/SHDN") (class "Default")
      (node (ref "U19") (pin "58") (pinfunction "PB6/I2C1_SCL/TIM4_CH1_58") (pintype "passive"))
      (node (ref "U2") (pin "8") (pinfunction "~{SHDN}_8") (pintype "passive"))
    )
    (net (code "35") (name "/SPI1_CS") (class "Default")
      (node (ref "U19") (pin "20") (pinfunction "PA4/SPI1_NSS/ADC4/DAC1_20") (pintype "passive"))
      (node (ref "U2") (pin "9") (pinfunction "~{CS}_9") (pintype "passive"))
    )
    (net (code "36") (name "/SPI1_MISO") (class "Default")
      (node (ref "U19") (pin "22") (pinfunction "PA6/SPI1_MISO/ADC6/TIM3_CH1/TIM8_BKIN_22") (pintype "passive"))
    )
    (net (code "37") (name "/SPI1_MOSI") (class "Default")
      (node (ref "U19") (pin "23") (pinfunction "PA7/SPI1_MOSI/ADC7/TIM3_CH2/TIM8_CH1N_23") (pintype "passive"))
      (node (ref "U2") (pin "13") (pinfunction "SDI_13") (pintype "passive"))
    )
    (net (code "38") (name "/SPI1_SCK") (class "Default")
      (node (ref "U19") (pin "21") (pinfunction "PA5/SPI1_SCK/ADC5/DAC2_21") (pintype "passive"))
      (node (ref "U2") (pin "12") (pinfunction "CLK_12") (pintype "passive"))
    )
    (net (code "39") (name "/SWCLK") (class "Default")
      (node (ref "P2") (pin "7") (pinfunction "7_7") (pintype "passive"))
      (node (ref "R21") (pin "1") (pinfunction "1_1") (pintype "passive"))
      (node (ref "U19") (pin "49") (pinfunction "PA14/JTCK/SWCLK_49") (pintype "passive"))
    )
    (net (code "40") (name "/SWDIO") (class "Default")
      (node (ref "P2") (pin "5") (pinfunction "5_5") (pintype "passive"))
      (node (ref "R22") (pin "1") (pinfunction "1_1") (pintype "passive"))
      (node (ref "U19") (pin "46") (pinfunction "PA13/JTMS/SWDIO_46") (pintype "passive"))
    )
    (net (code "41") (name "/SWO") (class "Default")
      (node (ref "P2") (pin "4") (pinfunction "4_4") (pintype "passive"))
      (node (ref "R20") (pin "1") (pinfunction "1_1") (pintype "passive"))
      (node (ref "U19") (pin "55") (pinfunction "PB3/JTDO/SPI3_SCK/I2S3_CK_55") (pintype "passive"))
    )
    (net (code "42") (name "/TX1") (class "Default")
      (node (ref "P1") (pin "2") (pinfunction "2_2") (pintype "passive"))
      (node (ref "U19") (pin "42") (pinfunction "PA9/U1_TX/TIM1_CH2_42") (pintype "passive"))
    )
    (net (code "43") (name "/TX3") (class "Default")
      (node (ref "P2") (pin "8") (pinfunction "8_8") (pintype "passive"))
      (node (ref "U19") (pin "29") (pinfunction "PB10/I2C2_SCL/U3_TX_29") (pintype "passive"))
    )
    (net (code "44") (name "/VOUT1") (class "Default")
      (node (ref "C21") (pin "2") (pinfunction "2_2") (pintype "passive"))
      (node (ref "C33") (pin "2") (pinfunction "2_2") (pintype "passive"))
      (node (ref "R45") (pin "2") (pinfunction "2_2") (pintype "passive"))
      (node (ref "U5") (pin "1") (pinfunction "OUT1_1") (pintype "passive"))
      (node (ref "U5") (pin "2") (pinfunction "IN1-_2") (pintype "passive"))
      (node (ref "U5") (pin "6") (pinfunction "IN2-_6") (pintype "passive"))
      (node (ref "U5") (pin "7") (pinfunction "OUT2_7") (pintype "passive"))
    )
    (net (code "45") (name "/VOUT2") (class "Default")
      (node (ref "C22") (pin "2") (pinfunction "2_2") (pintype "passive"))
      (node (ref "C34") (pin "2") (pinfunction "2_2") (pintype "passive"))
      (node (ref "R46") (pin "2") (pinfunction "2_2") (pintype "passive"))
      (node (ref "U6") (pin "1") (pinfunction "OUT1_1") (pintype "passive"))
      (node (ref "U6") (pin "2") (pinfunction "IN1-_2") (pintype "passive"))
      (node (ref "U6") (pin "6") (pinfunction "IN2-_6") (pintype "passive"))
      (node (ref "U6") (pin "7") (pinfunction "OUT2_7") (pintype "passive"))
    )
    (net (code "46") (name "/VOUT3") (class "Default")
      (node (ref "C23") (pin "2") (pinfunction "2_2") (pintype "passive"))
      (node (ref "C35") (pin "2") (pinfunction "2_2") (pintype "passive"))
      (node (ref "R47") (pin "2") (pinfunction "2_2") (pintype "passive"))
      (node (ref "U7") (pin "1") (pinfunction "OUT1_1") (pintype "passive"))
      (node (ref "U7") (pin "2") (pinfunction "IN1-_2") (pintype "passive"))
      (node (ref "U7") (pin "6") (pinfunction "IN2-_6") (pintype "passive"))
      (node (ref "U7") (pin "7") (pinfunction "OUT2_7") (pintype "passive"))
    )
    (net (code "47") (name "/VOUT4") (class "Default")
      (node (ref "C24") (pin "2") (pinfunction "2_2") (pintype "passive"))
      (node (ref "C36") (pin "2") (pinfunction "2_2") (pintype "passive"))
      (node (ref "R48") (pin "2") (pinfunction "2_2") (pintype "passive"))
      (node (ref "U8") (pin "1") (pinfunction "OUT1_1") (pintype "passive"))
      (node (ref "U8") (pin "2") (pinfunction "IN1-_2") (pintype "passive"))
      (node (ref "U8") (pin "6") (pinfunction "IN2-_6") (pintype "passive"))
      (node (ref "U8") (pin "7") (pinfunction "OUT2_7") (pintype "passive"))
    )
    (net (code "48") (name "/VOUT5") (class "Default")
      (node (ref "C25") (pin "2") (pinfunction "2_2") (pintype "passive"))
      (node (ref "C37") (pin "2") (pinfunction "2_2") (pintype "passive"))
      (node (ref "R49") (pin "2") (pinfunction "2_2") (pintype "passive"))
      (node (ref "U9") (pin "1") (pinfunction "OUT1_1") (pintype "passive"))
      (node (ref "U9") (pin "2") (pinfunction "IN1-_2") (pintype "passive"))
      (node (ref "U9") (pin "6") (pinfunction "IN2-_6") (pintype "passive"))
      (node (ref "U9") (pin "7") (pinfunction "OUT2_7") (pintype "passive"))
    )
    (net (code "49") (name "/VOUT6") (class "Default")
      (node (ref "C26") (pin "2") (pinfunction "2_2") (pintype "passive"))
      (node (ref "C38") (pin "2") (pinfunction "2_2") (pintype "passive"))
      (node (ref "R50") (pin "2") (pinfunction "2_2") (pintype "passive"))
      (node (ref "U10") (pin "1") (pinfunction "OUT1_1") (pintype "passive"))
      (node (ref "U10") (pin "2") (pinfunction "IN1-_2") (pintype "passive"))
      (node (ref "U10") (pin "6") (pinfunction "IN2-_6") (pintype "passive"))
      (node (ref "U10") (pin "7") (pinfunction "OUT2_7") (pintype "passive"))
    )
    (net (code "50") (name "/VOUT7") (class "Default")
      (node (ref "C27") (pin "2") (pinfunction "2_2") (pintype "passive"))
      (node (ref "C39") (pin "2") (pinfunction "2_2") (pintype "passive"))
      (node (ref "R51") (pin "2") (pinfunction "2_2") (pintype "passive"))
      (node (ref "U11") (pin "1") (pinfunction "OUT1_1") (pintype "passive"))
      (node (ref "U11") (pin "2") (pinfunction "IN1-_2") (pintype "passive"))
      (node (ref "U11") (pin "6") (pinfunction "IN2-_6") (pintype "passive"))
      (node (ref "U11") (pin "7") (pinfunction "OUT2_7") (pintype "passive"))
    )
    (net (code "51") (name "/VOUT8") (class "Default")
      (node (ref "C28") (pin "2") (pinfunction "2_2") (pintype "passive"))
      (node (ref "C40") (pin "2") (pinfunction "2_2") (pintype "passive"))
      (node (ref "R52") (pin "2") (pinfunction "2_2") (pintype "passive"))
      (node (ref "U12") (pin "1") (pinfunction "OUT1_1") (pintype "passive"))
      (node (ref "U12") (pin "2") (pinfunction "IN1-_2") (pintype "passive"))
      (node (ref "U12") (pin "6") (pinfunction "IN2-_6") (pintype "passive"))
      (node (ref "U12") (pin "7") (pinfunction "OUT2_7") (pintype "passive"))
    )
    (net (code "52") (name "/VOUT9") (class "Default")
      (node (ref "C29") (pin "2") (pinfunction "2_2") (pintype "passive"))
      (node (ref "C41") (pin "2") (pinfunction "2_2") (pintype "passive"))
      (node (ref "R53") (pin "2") (pinfunction "2_2") (pintype "passive"))
      (node (ref "U13") (pin "1") (pinfunction "OUT1_1") (pintype "passive"))
      (node (ref "U13") (pin "2") (pinfunction "IN1-_2") (pintype "passive"))
      (node (ref "U13") (pin "6") (pinfunction "IN2-_6") (pintype "passive"))
      (node (ref "U13") (pin "7") (pinfunction "OUT2_7") (pintype "passive"))
    )
    (net (code "53") (name "/VOUT10") (class "Default")
      (node (ref "C30") (pin "2") (pinfunction "2_2") (pintype "passive"))
      (node (ref "C42") (pin "2") (pinfunction "2_2") (pintype "passive"))
      (node (ref "R54") (pin "2") (pinfunction "2_2") (pintype "passive"))
      (node (ref "U14") (pin "1") (pinfunction "OUT1_1") (pintype "passive"))
      (node (ref "U14") (pin "2") (pinfunction "IN1-_2") (pintype "passive"))
      (node (ref "U14") (pin "6") (pinfunction "IN2-_6") (pintype "passive"))
      (node (ref "U14") (pin "7") (pinfunction "OUT2_7") (pintype "passive"))
    )
    (net (code "54") (name "/VOUT11") (class "Default")
      (node (ref "C31") (pin "2") (pinfunction "2_2") (pintype "passive"))
      (node (ref "C43") (pin "2") (pinfunction "2_2") (pintype "passive"))
      (node (ref "R55") (pin "2") (pinfunction "2_2") (pintype "passive"))
      (node (ref "U15") (pin "1") (pinfunction "OUT1_1") (pintype "passive"))
      (node (ref "U15") (pin "2") (pinfunction "IN1-_2") (pintype "passive"))
      (node (ref "U15") (pin "6") (pinfunction "IN2-_6") (pintype "passive"))
      (node (ref "U15") (pin "7") (pinfunction "OUT2_7") (pintype "passive"))
    )
    (net (code "55") (name "/VOUT12") (class "Default")
      (node (ref "C32") (pin "2") (pinfunction "2_2") (pintype "passive"))
      (node (ref "C44") (pin "2") (pinfunction "2_2") (pintype "passive"))
      (node (ref "R56") (pin "2") (pinfunction "2_2") (pintype "passive"))
      (node (ref "U16") (pin "1") (pinfunction "OUT1_1") (pintype "passive"))
      (node (ref "U16") (pin "2") (pinfunction "IN1-_2") (pintype "passive"))
      (node (ref "U16") (pin "6") (pinfunction "IN2-_6") (pintype "passive"))
      (node (ref "U16") (pin "7") (pinfunction "OUT2_7") (pintype "passive"))
    )
    (net (code "56") (name "GND") (class "Default")
      (node (ref "C1") (pin "2") (pintype "passive"))
      (node (ref "C10") (pin "1") (pinfunction "1_1") (pintype "passive"))
      (node (ref "C11") (pin "1") (pinfunction "1_1") (pintype "passive"))
      (node (ref "C12") (pin "1") (pinfunction "1_1") (pintype "passive"))
      (node (ref "C13") (pin "1") (pinfunction "1_1") (pintype "passive"))
      (node (ref "C14") (pin "1") (pinfunction "1_1") (pintype "passive"))
      (node (ref "C15") (pin "1") (pinfunction "1_1") (pintype "passive"))
      (node (ref "C16") (pin "2") (pinfunction "2_2") (pintype "passive"))
      (node (ref "C17") (pin "2") (pinfunction "2_2") (pintype "passive"))
      (node (ref "C18") (pin "1") (pinfunction "1_1") (pintype "passive"))
      (node (ref "C19") (pin "2") (pinfunction "2_2") (pintype "passive"))
      (node (ref "C2") (pin "2") (pinfunction "2_2") (pintype "passive"))
      (node (ref "C20") (pin "2") (pinfunction "2_2") (pintype "passive"))
      (node (ref "C21") (pin "1") (pinfunction "1_1") (pintype "passive"))
      (node (ref "C22") (pin "1") (pinfunction "1_1") (pintype "passive"))
      (node (ref "C23") (pin "1") (pinfunction "1_1") (pintype "passive"))
      (node (ref "C24") (pin "1") (pinfunction "1_1") (pintype "passive"))
      (node (ref "C25") (pin "1") (pinfunction "1_1") (pintype "passive"))
      (node (ref "C26") (pin "1") (pinfunction "1_1") (pintype "passive"))
      (node (ref "C27") (pin "1") (pinfunction "1_1") (pintype "passive"))
      (node (ref "C28") (pin "1") (pinfunction "1_1") (pintype "passive"))
      (node (ref "C29") (pin "1") (pinfunction "1_1") (pintype "passive"))
      (node (ref "C3") (pin "2") (pintype "passive"))
      (node (ref "C30") (pin "1") (pinfunction "1_1") (pintype "passive"))
      (node (ref "C31") (pin "1") (pinfunction "1_1") (pintype "passive"))
      (node (ref "C32") (pin "1") (pinfunction "1_1") (pintype "passive"))
      (node (ref "C33") (pin "1") (pinfunction "1_1") (pintype "passive"))
      (node (ref "C34") (pin "1") (pinfunction "1_1") (pintype "passive"))
      (node (ref "C35") (pin "1") (pinfunction "1_1") (pintype "passive"))
      (node (ref "C36") (pin "1") (pinfunction "1_1") (pintype "passive"))
      (node (ref "C37") (pin "1") (pinfunction "1_1") (pintype "passive"))
      (node (ref "C38") (pin "1") (pinfunction "1_1") (pintype "passive"))
      (node (ref "C39") (pin "1") (pinfunction "1_1") (pintype "passive"))
      (node (ref "C4") (pin "1") (pinfunction "1_1") (pintype "passive"))
      (node (ref "C40") (pin "1") (pinfunction "1_1") (pintype "passive"))
      (node (ref "C41") (pin "1") (pinfunction "1_1") (pintype "passive"))
      (node (ref "C42") (pin "1") (pinfunction "1_1") (pintype "passive"))
      (node (ref "C43") (pin "1") (pinfunction "1_1") (pintype "passive"))
      (node (ref "C44") (pin "1") (pinfunction "1_1") (pintype "passive"))
      (node (ref "C6") (pin "1") (pinfunction "1_1") (pintype "passive"))
      (node (ref "C7") (pin "1") (pinfunction "1_1") (pintype "passive"))
      (node (ref "C8") (pin "1") (pinfunction "1_1") (pintype "passive"))
      (node (ref "C9") (pin "2") (pinfunction "GND_2") (pintype "passive"))
      (node (ref "CT1") (pin "2") (pinfunction "Negative_2") (pintype "passive"))
      (node (ref "CT2") (pin "2") (pinfunction "Negative_2") (pintype "passive"))
      (node (ref "D1") (pin "2") (pinfunction "T-_2") (pintype "passive"))
      (node (ref "D10d") (pin "2") (pinfunction "K_2") (pintype "passive"))
      (node (ref "D11d") (pin "2") (pinfunction "K_2") (pintype "passive"))
      (node (ref "D12d") (pin "2") (pinfunction "K_2") (pintype "passive"))
      (node (ref "D1d") (pin "2") (pinfunction "K_2") (pintype "passive"))
      (node (ref "D2d") (pin "2") (pinfunction "K_2") (pintype "passive"))
      (node (ref "D3d") (pin "2") (pinfunction "K_2") (pintype "passive"))
      (node (ref "D4d") (pin "2") (pinfunction "K_2") (pintype "passive"))
      (node (ref "D5d") (pin "2") (pinfunction "K_2") (pintype "passive"))
      (node (ref "D6d") (pin "2") (pinfunction "K_2") (pintype "passive"))
      (node (ref "D7d") (pin "2") (pinfunction "K_2") (pintype "passive"))
      (node (ref "D8d") (pin "2") (pinfunction "K_2") (pintype "passive"))
      (node (ref "D9d") (pin "2") (pinfunction "K_2") (pintype "passive"))
      (node (ref "P1") (pin "3") (pinfunction "3_3") (pintype "passive"))
      (node (ref "P2") (pin "6") (pinfunction "6_6") (pintype "passive"))
      (node (ref "P2") (pin "9") (pinfunction "9_9") (pintype "passive"))
      (node (ref "P8") (pin "3") (pinfunction "3_3") (pintype "passive"))
      (node (ref "R1") (pin "1") (pinfunction "1_1") (pintype "passive"))
      (node (ref "R21") (pin "2") (pinfunction "2_2") (pintype "passive"))
      (node (ref "R34") (pin "2") (pinfunction "2_2") (pintype "passive"))
      (node (ref "R39") (pin "1") (pinfunction "1_1") (pintype "passive"))
      (node (ref "R4") (pin "1") (pinfunction "1_1") (pintype "passive"))
      (node (ref "R40") (pin "1") (pinfunction "1_1") (pintype "passive"))
      (node (ref "R8") (pin "1") (pinfunction "1_1") (pintype "passive"))
      (node (ref "RESET_B") (pin "1") (pinfunction "1_1") (pintype "passive"))
      (node (ref "U1") (pin "3") (pinfunction "GND_3") (pintype "power_in"))
      (node (ref "U1") (pin "5") (pinfunction "~{ON}/OFF_5") (pintype "input"))
      (node (ref "U10") (pin "4") (pinfunction "GND_4") (pintype "passive"))
      (node (ref "U11") (pin "4") (pinfunction "GND_4") (pintype "passive"))
      (node (ref "U12") (pin "4") (pinfunction "GND_4") (pintype "passive"))
      (node (ref "U13") (pin "4") (pinfunction "GND_4") (pintype "passive"))
      (node (ref "U14") (pin "4") (pinfunction "GND_4") (pintype "passive"))
      (node (ref "U15") (pin "4") (pinfunction "GND_4") (pintype "passive"))
      (node (ref "U16") (pin "4") (pinfunction "GND_4") (pintype "passive"))
      (node (ref "U17") (pin "1") (pinfunction "GND_1") (pintype "passive"))
      (node (ref "U18") (pin "1") (pinfunction "1_1") (pintype "passive"))
      (node (ref "U19") (pin "12") (pinfunction "VSSA_12") (pintype "passive"))
      (node (ref "U19") (pin "18") (pinfunction "VSS_18") (pintype "passive"))
      (node (ref "U19") (pin "31") (pinfunction "VSS_31") (pintype "passive"))
      (node (ref "U19") (pin "47") (pinfunction "VSS_47") (pintype "passive"))
      (node (ref "U19") (pin "63") (pinfunction "VSS_63") (pintype "passive"))
      (node (ref "U2") (pin "10") (pinfunction "GND_10") (pintype "passive"))
      (node (ref "U3") (pin "4") (pinfunction "-_4") (pintype "passive"))
      (node (ref "U4") (pin "4") (pinfunction "-_4") (pintype "passive"))
      (node (ref "U5") (pin "4") (pinfunction "GND_4") (pintype "passive"))
      (node (ref "U6") (pin "4") (pinfunction "GND_4") (pintype "passive"))
      (node (ref "U7") (pin "4") (pinfunction "GND_4") (pintype "passive"))
      (node (ref "U8") (pin "4") (pinfunction "GND_4") (pintype "passive"))
      (node (ref "U9") (pin "4") (pinfunction "GND_4") (pintype "passive"))
      (node (ref "V1") (pin "1") (pinfunction "A_1") (pintype "passive"))
    )
    (net (code "57") (name "Net-(D1-B-)") (class "Default")
      (node (ref "D1") (pin "1") (pinfunction "B-_1") (pintype "passive"))
      (node (ref "R5") (pin "1") (pinfunction "1_1") (pintype "passive"))
    )
    (net (code "58") (name "Net-(D1a-A)") (class "Default")
      (node (ref "D1a") (pin "1") (pinfunction "A_1") (pintype "passive"))
      (node (ref "R45") (pin "1") (pinfunction "1_1") (pintype "passive"))
    )
    (net (code "59") (name "Net-(D1a-K)") (class "Default")
      (node (ref "D1a") (pin "2") (pinfunction "K_2") (pintype "passive"))
      (node (ref "D1b") (pin "1") (pinfunction "A_1") (pintype "passive"))
    )
    (net (code "60") (name "Net-(D1b-K)") (class "Default")
      (node (ref "D1b") (pin "2") (pinfunction "K_2") (pintype "passive"))
      (node (ref "D1c") (pin "1") (pinfunction "A_1") (pintype "passive"))
    )
    (net (code "61") (name "Net-(D1c-K)") (class "Default")
      (node (ref "D1c") (pin "2") (pinfunction "K_2") (pintype "passive"))
      (node (ref "D1d") (pin "1") (pinfunction "A_1") (pintype "passive"))
    )
    (net (code "62") (name "Net-(D2a-A)") (class "Default")
      (node (ref "D2a") (pin "1") (pinfunction "A_1") (pintype "passive"))
      (node (ref "R46") (pin "1") (pinfunction "1_1") (pintype "passive"))
    )
    (net (code "63") (name "Net-(D2a-K)") (class "Default")
      (node (ref "D2a") (pin "2") (pinfunction "K_2") (pintype "passive"))
      (node (ref "D2b") (pin "1") (pinfunction "A_1") (pintype "passive"))
    )
    (net (code "64") (name "Net-(D2b-K)") (class "Default")
      (node (ref "D2b") (pin "2") (pinfunction "K_2") (pintype "passive"))
      (node (ref "D2c") (pin "1") (pinfunction "A_1") (pintype "passive"))
    )
    (net (code "65") (name "Net-(D2c-K)") (class "Default")
      (node (ref "D2c") (pin "2") (pinfunction "K_2") (pintype "passive"))
      (node (ref "D2d") (pin "1") (pinfunction "A_1") (pintype "passive"))
    )
    (net (code "66") (name "Net-(D3a-A)") (class "Default")
      (node (ref "D3a") (pin "1") (pinfunction "A_1") (pintype "passive"))
      (node (ref "R47") (pin "1") (pinfunction "1_1") (pintype "passive"))
    )
    (net (code "67") (name "Net-(D3a-K)") (class "Default")
      (node (ref "D3a") (pin "2") (pinfunction "K_2") (pintype "passive"))
      (node (ref "D3b") (pin "1") (pinfunction "A_1") (pintype "passive"))
    )
    (net (code "68") (name "Net-(D3b-K)") (class "Default")
      (node (ref "D3b") (pin "2") (pinfunction "K_2") (pintype "passive"))
      (node (ref "D3c") (pin "1") (pinfunction "A_1") (pintype "passive"))
    )
    (net (code "69") (name "Net-(D3c-K)") (class "Default")
      (node (ref "D3c") (pin "2") (pinfunction "K_2") (pintype "passive"))
      (node (ref "D3d") (pin "1") (pinfunction "A_1") (pintype "passive"))
    )
    (net (code "70") (name "Net-(D4a-A)") (class "Default")
      (node (ref "D4a") (pin "1") (pinfunction "A_1") (pintype "passive"))
      (node (ref "R48") (pin "1") (pinfunction "1_1") (pintype "passive"))
    )
    (net (code "71") (name "Net-(D4a-K)") (class "Default")
      (node (ref "D4a") (pin "2") (pinfunction "K_2") (pintype "passive"))
      (node (ref "D4b") (pin "1") (pinfunction "A_1") (pintype "passive"))
    )
    (net (code "72") (name "Net-(D4b-K)") (class "Default")
      (node (ref "D4b") (pin "2") (pinfunction "K_2") (pintype "passive"))
      (node (ref "D4c") (pin "1") (pinfunction "A_1") (pintype "passive"))
    )
    (net (code "73") (name "Net-(D4c-K)") (class "Default")
      (node (ref "D4c") (pin "2") (pinfunction "K_2") (pintype "passive"))
      (node (ref "D4d") (pin "1") (pinfunction "A_1") (pintype "passive"))
    )
    (net (code "74") (name "Net-(D5a-A)") (class "Default")
      (node (ref "D5a") (pin "1") (pinfunction "A_1") (pintype "passive"))
      (node (ref "R49") (pin "1") (pinfunction "1_1") (pintype "passive"))
    )
    (net (code "75") (name "Net-(D5a-K)") (class "Default")
      (node (ref "D5a") (pin "2") (pinfunction "K_2") (pintype "passive"))
      (node (ref "D5b") (pin "1") (pinfunction "A_1") (pintype "passive"))
    )
    (net (code "76") (name "Net-(D5b-K)") (class "Default")
      (node (ref "D5b") (pin "2") (pinfunction "K_2") (pintype "passive"))
      (node (ref "D5c") (pin "1") (pinfunction "A_1") (pintype "passive"))
    )
    (net (code "77") (name "Net-(D5c-K)") (class "Default")
      (node (ref "D5c") (pin "2") (pinfunction "K_2") (pintype "passive"))
      (node (ref "D5d") (pin "1") (pinfunction "A_1") (pintype "passive"))
    )
    (net (code "78") (name "Net-(D6-A)") (class "Default")
      (node (ref "D6") (pin "1") (pinfunction "A_1") (pintype "passive"))
      (node (ref "D7") (pin "2") (pinfunction "K_2") (pintype "passive"))
    )
    (net (code "79") (name "Net-(D6a-A)") (class "Default")
      (node (ref "D6a") (pin "1") (pinfunction "A_1") (pintype "passive"))
      (node (ref "R50") (pin "1") (pinfunction "1_1") (pintype "passive"))
    )
    (net (code "80") (name "Net-(D6a-K)") (class "Default")
      (node (ref "D6a") (pin "2") (pinfunction "K_2") (pintype "passive"))
      (node (ref "D6b") (pin "1") (pinfunction "A_1") (pintype "passive"))
    )
    (net (code "81") (name "Net-(D6b-K)") (class "Default")
      (node (ref "D6b") (pin "2") (pinfunction "K_2") (pintype "passive"))
      (node (ref "D6c") (pin "1") (pinfunction "A_1") (pintype "passive"))
    )
    (net (code "82") (name "Net-(D6c-K)") (class "Default")
      (node (ref "D6c") (pin "2") (pinfunction "K_2") (pintype "passive"))
      (node (ref "D6d") (pin "1") (pinfunction "A_1") (pintype "passive"))
    )
    (net (code "83") (name "Net-(D7a-A)") (class "Default")
      (node (ref "D7a") (pin "1") (pinfunction "A_1") (pintype "passive"))
      (node (ref "R51") (pin "1") (pinfunction "1_1") (pintype "passive"))
    )
    (net (code "84") (name "Net-(D7a-K)") (class "Default")
      (node (ref "D7a") (pin "2") (pinfunction "K_2") (pintype "passive"))
      (node (ref "D7b") (pin "1") (pinfunction "A_1") (pintype "passive"))
    )
    (net (code "85") (name "Net-(D7b-K)") (class "Default")
      (node (ref "D7b") (pin "2") (pinfunction "K_2") (pintype "passive"))
      (node (ref "D7c") (pin "1") (pinfunction "A_1") (pintype "passive"))
    )
    (net (code "86") (name "Net-(D7c-K)") (class "Default")
      (node (ref "D7c") (pin "2") (pinfunction "K_2") (pintype "passive"))
      (node (ref "D7d") (pin "1") (pinfunction "A_1") (pintype "passive"))
    )
    (net (code "87") (name "Net-(D8-K)") (class "Default")
      (node (ref "D8") (pin "2") (pinfunction "K_2") (pintype "passive"))
      (node (ref "U19") (pin "1") (pinfunction "VBAT_1") (pintype "passive"))
    )
    (net (code "88") (name "Net-(D8a-A)") (class "Default")
      (node (ref "D8a") (pin "1") (pinfunction "A_1") (pintype "passive"))
      (node (ref "R52") (pin "1") (pinfunction "1_1") (pintype "passive"))
    )
    (net (code "89") (name "Net-(D8a-K)") (class "Default")
      (node (ref "D8a") (pin "2") (pinfunction "K_2") (pintype "passive"))
      (node (ref "D8b") (pin "1") (pinfunction "A_1") (pintype "passive"))
    )
    (net (code "90") (name "Net-(D8b-K)") (class "Default")
      (node (ref "D8b") (pin "2") (pinfunction "K_2") (pintype "passive"))
      (node (ref "D8c") (pin "1") (pinfunction "A_1") (pintype "passive"))
    )
    (net (code "91") (name "Net-(D8c-K)") (class "Default")
      (node (ref "D8c") (pin "2") (pinfunction "K_2") (pintype "passive"))
      (node (ref "D8d") (pin "1") (pinfunction "A_1") (pintype "passive"))
    )
    (net (code "92") (name "Net-(D9a-A)") (class "Default")
      (node (ref "D9a") (pin "1") (pinfunction "A_1") (pintype "passive"))
      (node (ref "R53") (pin "1") (pinfunction "1_1") (pintype "passive"))
    )
    (net (code "93") (name "Net-(D9a-K)") (class "Default")
      (node (ref "D9a") (pin "2") (pinfunction "K_2") (pintype "passive"))
      (node (ref "D9b") (pin "1") (pinfunction "A_1") (pintype "passive"))
    )
    (net (code "94") (name "Net-(D9b-K)") (class "Default")
      (node (ref "D9b") (pin "2") (pinfunction "K_2") (pintype "passive"))
      (node (ref "D9c") (pin "1") (pinfunction "A_1") (pintype "passive"))
    )
    (net (code "95") (name "Net-(D9c-K)") (class "Default")
      (node (ref "D9c") (pin "2") (pinfunction "K_2") (pintype "passive"))
      (node (ref "D9d") (pin "1") (pinfunction "A_1") (pintype "passive"))
    )
    (net (code "96") (name "Net-(D10a-A)") (class "Default")
      (node (ref "D10a") (pin "1") (pinfunction "A_1") (pintype "passive"))
      (node (ref "R54") (pin "1") (pinfunction "1_1") (pintype "passive"))
    )
    (net (code "97") (name "Net-(D10a-K)") (class "Default")
      (node (ref "D10a") (pin "2") (pinfunction "K_2") (pintype "passive"))
      (node (ref "D10b") (pin "1") (pinfunction "A_1") (pintype "passive"))
    )
    (net (code "98") (name "Net-(D10b-K)") (class "Default")
      (node (ref "D10b") (pin "2") (pinfunction "K_2") (pintype "passive"))
      (node (ref "D10c") (pin "1") (pinfunction "A_1") (pintype "passive"))
    )
    (net (code "99") (name "Net-(D10c-K)") (class "Default")
      (node (ref "D10c") (pin "2") (pinfunction "K_2") (pintype "passive"))
      (node (ref "D10d") (pin "1") (pinfunction "A_1") (pintype "passive"))
    )
    (net (code "100") (name "Net-(D11a-A)") (class "Default")
      (node (ref "D11a") (pin "1") (pinfunction "A_1") (pintype "passive"))
      (node (ref "R55") (pin "1") (pinfunction "1_1") (pintype "passive"))
    )
    (net (code "101") (name "Net-(D11a-K)") (class "Default")
      (node (ref "D11a") (pin "2") (pinfunction "K_2") (pintype "passive"))
      (node (ref "D11b") (pin "1") (pinfunction "A_1") (pintype "passive"))
    )
    (net (code "102") (name "Net-(D11b-K)") (class "Default")
      (node (ref "D11b") (pin "2") (pinfunction "K_2") (pintype "passive"))
      (node (ref "D11c") (pin "1") (pinfunction "A_1") (pintype "passive"))
    )
    (net (code "103") (name "Net-(D11c-K)") (class "Default")
      (node (ref "D11c") (pin "2") (pinfunction "K_2") (pintype "passive"))
      (node (ref "D11d") (pin "1") (pinfunction "A_1") (pintype "passive"))
    )
    (net (code "104") (name "Net-(D12a-A)") (class "Default")
      (node (ref "D12a") (pin "1") (pinfunction "A_1") (pintype "passive"))
      (node (ref "R56") (pin "1") (pinfunction "1_1") (pintype "passive"))
    )
    (net (code "105") (name "Net-(D12a-K)") (class "Default")
      (node (ref "D12a") (pin "2") (pinfunction "K_2") (pintype "passive"))
      (node (ref "D12b") (pin "1") (pinfunction "A_1") (pintype "passive"))
    )
    (net (code "106") (name "Net-(D12b-K)") (class "Default")
      (node (ref "D12b") (pin "2") (pinfunction "K_2") (pintype "passive"))
      (node (ref "D12c") (pin "1") (pinfunction "A_1") (pintype "passive"))
    )
    (net (code "107") (name "Net-(D12c-K)") (class "Default")
      (node (ref "D12c") (pin "2") (pinfunction "K_2") (pintype "passive"))
      (node (ref "D12d") (pin "1") (pinfunction "A_1") (pintype "passive"))
    )
    (net (code "108") (name "Net-(LED1-K)") (class "Default")
      (node (ref "LED1") (pin "2") (pinfunction "K_2") (pintype "passive"))
      (node (ref "R38") (pin "2") (pinfunction "2_2") (pintype "passive"))
    )
    (net (code "109") (name "Net-(LED2-K)") (class "Default")
      (node (ref "LED2") (pin "2") (pinfunction "K_2") (pintype "passive"))
      (node (ref "R37") (pin "2") (pinfunction "2_2") (pintype "passive"))
    )
    (net (code "110") (name "Net-(LED3-K)") (class "Default")
      (node (ref "LED3") (pin "2") (pinfunction "K_2") (pintype "passive"))
      (node (ref "R36") (pin "2") (pinfunction "2_2") (pintype "passive"))
    )
    (net (code "111") (name "Net-(POWER1-K)") (class "Default")
      (node (ref "POWER1") (pin "2") (pinfunction "K_2") (pintype "passive"))
      (node (ref "R39") (pin "2") (pinfunction "2_2") (pintype "passive"))
    )
    (net (code "112") (name "Net-(R33-Pad1)") (class "Default")
      (node (ref "R33") (pin "1") (pinfunction "1_1") (pintype "passive"))
      (node (ref "U18") (pin "2") (pinfunction "2_2") (pintype "passive"))
    )
    (net (code "113") (name "Net-(R41-Pad1)") (class "Default")
      (node (ref "R41") (pin "1") (pinfunction "1_1") (pintype "passive"))
      (node (ref "R42") (pin "1") (pinfunction "1_1") (pintype "passive"))
      (node (ref "R8") (pin "3") (pinfunction "3_3") (pintype "passive"))
    )
    (net (code "114") (name "Net-(U1-FB)") (class "Default")
      (node (ref "C5") (pin "2") (pinfunction "2_2") (pintype "passive"))
      (node (ref "R1") (pin "2") (pinfunction "2_2") (pintype "passive"))
      (node (ref "R2") (pin "1") (pinfunction "1_1") (pintype "passive"))
      (node (ref "U1") (pin "4") (pinfunction "FB_4") (pintype "input"))
    )
    (net (code "115") (name "Net-(U1-OUT)") (class "Default")
      (node (ref "L1") (pin "1") (pinfunction "1_1") (pintype "passive"))
      (node (ref "U1") (pin "2") (pinfunction "OUT_2") (pintype "power_in"))
      (node (ref "V1") (pin "2") (pinfunction "K_2") (pintype "passive"))
    )
    (net (code "116") (name "Net-(U2-VRefH)") (class "Default")
      (node (ref "R43") (pin "2") (pinfunction "2_2") (pintype "passive"))
      (node (ref "R44") (pin "1") (pinfunction "1_1") (pintype "passive"))
      (node (ref "U2") (pin "1") (pinfunction "VRefH_1") (pintype "passive"))
    )
    (net (code "117") (name "Net-(U2-VRefL)") (class "Default")
      (node (ref "R7") (pin "1") (pinfunction "1_1") (pintype "passive"))
      (node (ref "U2") (pin "11") (pinfunction "VRefL_11") (pintype "passive"))
      (node (ref "U4") (pin "8") (pinfunction "+_8") (pintype "passive"))
    )
    (net (code "118") (name "Net-(U3-+)") (class "Default")
      (node (ref "R41") (pin "2") (pinfunction "2_2") (pintype "passive"))
      (node (ref "R43") (pin "1") (pinfunction "1_1") (pintype "passive"))
      (node (ref "R6") (pin "1") (pinfunction "1_1") (pintype "passive"))
      (node (ref "U3") (pin "8") (pinfunction "+_8") (pintype "passive"))
    )
    (net (code "119") (name "Net-(U3-ADJ)") (class "Default")
      (node (ref "R8") (pin "2") (pinfunction "2_2") (pintype "passive"))
      (node (ref "U3") (pin "5") (pinfunction "ADJ_5") (pintype "passive"))
    )
    (net (code "120") (name "Net-(U19-PC14{slash}OSC32)") (class "Default")
      (node (ref "C12") (pin "2") (pinfunction "2_2") (pintype "passive"))
      (node (ref "U19") (pin "3") (pinfunction "PC14/OSC32_3") (pintype "passive"))
      (node (ref "Y1") (pin "1") (pinfunction "OSC1_1") (pintype "passive"))
    )
    (net (code "121") (name "Net-(U19-PC15{slash}OSC32)") (class "Default")
      (node (ref "C13") (pin "2") (pinfunction "2_2") (pintype "passive"))
      (node (ref "U19") (pin "4") (pinfunction "PC15/OSC32_4") (pintype "passive"))
      (node (ref "Y1") (pin "2") (pinfunction "OSC2_2") (pintype "passive"))
    )
    (net (code "122") (name "Net-(U19-PD0{slash}OSCIN)") (class "Default")
      (node (ref "C14") (pin "2") (pinfunction "2_2") (pintype "passive"))
      (node (ref "R35") (pin "1") (pinfunction "1_1") (pintype "passive"))
      (node (ref "U19") (pin "5") (pinfunction "PD0/OSCIN_5") (pintype "passive"))
      (node (ref "Y2") (pin "1") (pinfunction "OSC1_1") (pintype "passive"))
    )
    (net (code "123") (name "Net-(U19-PD1{slash}OSCOUT)") (class "Default")
      (node (ref "C15") (pin "2") (pinfunction "2_2") (pintype "passive"))
      (node (ref "R35") (pin "2") (pinfunction "2_2") (pintype "passive"))
      (node (ref "U19") (pin "6") (pinfunction "PD1/OSCOUT_6") (pintype "passive"))
      (node (ref "Y2") (pin "2") (pinfunction "OSC2_2") (pintype "passive"))
    )
    (net (code "124") (name "Net-(U19-VDDA)") (class "Default")
      (node (ref "C16") (pin "1") (pinfunction "1_1") (pintype "passive"))
      (node (ref "C17") (pin "1") (pinfunction "1_1") (pintype "passive"))
      (node (ref "L2") (pin "2") (pinfunction "2_2") (pintype "passive"))
      (node (ref "U19") (pin "13") (pinfunction "VDDA_13") (pintype "passive"))
    )
    (net (code "125") (name "PG") (class "Default")
      (node (ref "C2") (pin "1") (pinfunction "1_1") (pintype "passive"))
      (node (ref "R4") (pin "2") (pinfunction "2_2") (pintype "passive"))
    )
    (net (code "126") (name "VCC5V") (class "Default")
      (node (ref "C6") (pin "2") (pinfunction "2_2") (pintype "passive"))
      (node (ref "C8") (pin "2") (pinfunction "2_2") (pintype "passive"))
      (node (ref "CT2") (pin "1") (pinfunction "Positive_1") (pintype "passive"))
      (node (ref "D6") (pin "2") (pinfunction "K_2") (pintype "passive"))
      (node (ref "P1") (pin "4") (pinfunction "4_4") (pintype "passive"))
      (node (ref "P2") (pin "1") (pinfunction "1_1") (pintype "passive"))
      (node (ref "R42") (pin "2") (pinfunction "2_2") (pintype "passive"))
      (node (ref "R44") (pin "2") (pinfunction "2_2") (pintype "passive"))
      (node (ref "U17") (pin "3") (pinfunction "IN_3") (pintype "passive"))
      (node (ref "U2") (pin "20") (pinfunction "VDD_20") (pintype "passive"))
    )
    (net (code "127") (name "VCC6") (class "Default")
      (node (ref "C3") (pin "1") (pintype "passive"))
      (node (ref "C4") (pin "2") (pinfunction "2_2") (pintype "passive"))
      (node (ref "C5") (pin "1") (pinfunction "1_1") (pintype "passive"))
      (node (ref "CT1") (pin "1") (pinfunction "Positive_1") (pintype "passive"))
      (node (ref "D7") (pin "1") (pinfunction "A_1") (pintype "passive"))
      (node (ref "L1") (pin "2") (pinfunction "2_2") (pintype "passive"))
      (node (ref "R2") (pin "2") (pinfunction "2_2") (pintype "passive"))
      (node (ref "R5") (pin "2") (pinfunction "2_2") (pintype "passive"))
      (node (ref "R6") (pin "2") (pinfunction "2_2") (pintype "passive"))
      (node (ref "R7") (pin "2") (pinfunction "2_2") (pintype "passive"))
      (node (ref "U10") (pin "8") (pinfunction "VCC_8") (pintype "passive"))
      (node (ref "U11") (pin "8") (pinfunction "VCC_8") (pintype "passive"))
      (node (ref "U12") (pin "8") (pinfunction "VCC_8") (pintype "passive"))
      (node (ref "U13") (pin "8") (pinfunction "VCC_8") (pintype "passive"))
      (node (ref "U14") (pin "8") (pinfunction "VCC_8") (pintype "passive"))
      (node (ref "U15") (pin "8") (pinfunction "VCC_8") (pintype "passive"))
      (node (ref "U16") (pin "8") (pinfunction "VCC_8") (pintype "passive"))
      (node (ref "U5") (pin "8") (pinfunction "VCC_8") (pintype "passive"))
      (node (ref "U6") (pin "8") (pinfunction "VCC_8") (pintype "passive"))
      (node (ref "U7") (pin "8") (pinfunction "VCC_8") (pintype "passive"))
      (node (ref "U8") (pin "8") (pinfunction "VCC_8") (pintype "passive"))
      (node (ref "U9") (pin "8") (pinfunction "VCC_8") (pintype "passive"))
    )
    (net (code "128") (name "VCC24V") (class "Default")
      (node (ref "C1") (pin "1") (pintype "passive"))
      (node (ref "P8") (pin "1") (pinfunction "1_1") (pintype "passive"))
      (node (ref "P8") (pin "2") (pinfunction "2_2") (pintype "passive"))
      (node (ref "U1") (pin "1") (pinfunction "IN_1") (pintype "power_in"))
    )
    (net (code "129") (name "VDD33V") (class "Default")
      (node (ref "C10") (pin "2") (pinfunction "2_2") (pintype "passive"))
      (node (ref "C18") (pin "2") (pinfunction "2_2") (pintype "passive"))
      (node (ref "C19") (pin "1") (pinfunction "1_1") (pintype "passive"))
      (node (ref "C20") (pin "1") (pinfunction "1_1") (pintype "passive"))
      (node (ref "C7") (pin "2") (pinfunction "2_2") (pintype "passive"))
      (node (ref "C9") (pin "1") (pinfunction "VCC_1") (pintype "passive"))
      (node (ref "D5") (pin "2") (pinfunction "K_2") (pintype "passive"))
      (node (ref "D8") (pin "1") (pinfunction "A_1") (pintype "passive"))
      (node (ref "L2") (pin "1") (pinfunction "1_1") (pintype "passive"))
      (node (ref "LED1") (pin "1") (pinfunction "A_1") (pintype "passive"))
      (node (ref "LED2") (pin "1") (pinfunction "A_1") (pintype "passive"))
      (node (ref "LED3") (pin "1") (pinfunction "A_1") (pintype "passive"))
      (node (ref "P2") (pin "3") (pinfunction "3_3") (pintype "passive"))
      (node (ref "POWER1") (pin "1") (pinfunction "A_1") (pintype "passive"))
      (node (ref "R20") (pin "2") (pinfunction "2_2") (pintype "passive"))
      (node (ref "R22") (pin "2") (pinfunction "2_2") (pintype "passive"))
      (node (ref "R32") (pin "2") (pinfunction "2_2") (pintype "passive"))
      (node (ref "U17") (pin "2") (pinfunction "OUT_2") (pintype "passive"))
      (node (ref "U17") (pin "4") (pinfunction "OUT_4") (pintype "passive"))
      (node (ref "U18") (pin "4") (pinfunction "4_4") (pintype "passive"))
      (node (ref "U19") (pin "19") (pinfunction "VDD_19") (pintype "passive"))
      (node (ref "U19") (pin "32") (pinfunction "VDD_32") (pintype "passive"))
      (node (ref "U19") (pin "48") (pinfunction "VDD_48") (pintype "passive"))
      (node (ref "U19") (pin "64") (pinfunction "VDD_64") (pintype "passive"))
    )
    (net (code "130") (name "unconnected-(U3-NC-Pad1)") (class "Default")
      (node (ref "U3") (pin "1") (pinfunction "NC_1") (pintype "passive"))
    )
    (net (code "131") (name "unconnected-(U3-NC-Pad2)") (class "Default")
      (node (ref "U3") (pin "2") (pinfunction "NC_2") (pintype "passive"))
    )
    (net (code "132") (name "unconnected-(U3-NC-Pad3)") (class "Default")
      (node (ref "U3") (pin "3") (pinfunction "NC_3") (pintype "passive"))
    )
    (net (code "133") (name "unconnected-(U3-NC-Pad6)") (class "Default")
      (node (ref "U3") (pin "6") (pinfunction "NC_6") (pintype "passive"))
    )
    (net (code "134") (name "unconnected-(U3-NC-Pad7)") (class "Default")
      (node (ref "U3") (pin "7") (pinfunction "NC_7") (pintype "passive"))
    )
    (net (code "135") (name "unconnected-(U4-ADJ-Pad5)") (class "Default")
      (node (ref "U4") (pin "5") (pinfunction "ADJ_5") (pintype "passive"))
    )
    (net (code "136") (name "unconnected-(U4-NC-Pad1)") (class "Default")
      (node (ref "U4") (pin "1") (pinfunction "NC_1") (pintype "passive"))
    )
    (net (code "137") (name "unconnected-(U4-NC-Pad2)") (class "Default")
      (node (ref "U4") (pin "2") (pinfunction "NC_2") (pintype "passive"))
    )
    (net (code "138") (name "unconnected-(U4-NC-Pad3)") (class "Default")
      (node (ref "U4") (pin "3") (pinfunction "NC_3") (pintype "passive"))
    )
    (net (code "139") (name "unconnected-(U4-NC-Pad6)") (class "Default")
      (node (ref "U4") (pin "6") (pinfunction "NC_6") (pintype "passive"))
    )
    (net (code "140") (name "unconnected-(U4-NC-Pad7)") (class "Default")
      (node (ref "U4") (pin "7") (pinfunction "NC_7") (pintype "passive"))
    )
    (net (code "141") (name "unconnected-(U19-PA8{slash}TIM1_CH1{slash}MCO-Pad41)") (class "Default")
      (node (ref "U19") (pin "41") (pinfunction "PA8/TIM1_CH1/MCO_41") (pintype "passive"))
    )
    (net (code "142") (name "unconnected-(U19-PA11{slash}CAN_RX{slash}USBDM{slash}TIM1_CH4-Pad44)") (class "Default")
      (node (ref "U19") (pin "44") (pinfunction "PA11/CAN_RX/USBDM/TIM1_CH4_44") (pintype "passive"))
    )
    (net (code "143") (name "unconnected-(U19-PA12{slash}CAN_TX{slash}USBDP{slash}TIM1_ETR-Pad45)") (class "Default")
      (node (ref "U19") (pin "45") (pinfunction "PA12/CAN_TX/USBDP/TIM1_ETR_45") (pintype "passive"))
    )
    (net (code "144") (name "unconnected-(U19-PA15{slash}JTDI{slash}SPI3_NSS{slash}I2S3_WS-Pad50)") (class "Default")
      (node (ref "U19") (pin "50") (pinfunction "PA15/JTDI/SPI3_NSS/I2S3_WS_50") (pintype "passive"))
    )
    (net (code "145") (name "unconnected-(U19-PB4{slash}JNTRST{slash}SPI3_MISO-Pad56)") (class "Default")
      (node (ref "U19") (pin "56") (pinfunction "PB4/JNTRST/SPI3_MISO_56") (pintype "passive"))
    )
    (net (code "146") (name "unconnected-(U19-PB5{slash}I2C1_SMBA{slash}SPI3_MOSI{slash}I2S3_SD-Pad57)") (class "Default")
      (node (ref "U19") (pin "57") (pinfunction "PB5/I2C1_SMBA/SPI3_MOSI/I2S3_SD_57") (pintype "passive"))
    )
    (net (code "147") (name "unconnected-(U19-PB12{slash}SPI2_NSS{slash}I2S2_WS{slash}I2C2_SMBAI{slash}TIM1_BKIN-Pad33)") (class "Default")
      (node (ref "U19") (pin "33") (pinfunction "PB12/SPI2_NSS/I2S2_WS/I2C2_SMBAI/TIM1_BKIN_33") (pintype "passive"))
    )
    (net (code "148") (name "unconnected-(U19-PB13{slash}SPI2_SCK{slash}I2S2_CK{slash}TIM1_CH1N-Pad34)") (class "Default")
      (node (ref "U19") (pin "34") (pinfunction "PB13/SPI2_SCK/I2S2_CK/TIM1_CH1N_34") (pintype "passive"))
    )
    (net (code "149") (name "unconnected-(U19-PB14{slash}SPI2_MISO{slash}TIM1_CH2N-Pad35)") (class "Default")
      (node (ref "U19") (pin "35") (pinfunction "PB14/SPI2_MISO/TIM1_CH2N_35") (pintype "passive"))
    )
    (net (code "150") (name "unconnected-(U19-PB15{slash}SPI2_MOSI{slash}I2S2_SD{slash}TIM1_CH3N-Pad36)") (class "Default")
      (node (ref "U19") (pin "36") (pinfunction "PB15/SPI2_MOSI/I2S2_SD/TIM1_CH3N_36") (pintype "passive"))
    )
    (net (code "151") (name "unconnected-(U19-PC6{slash}I2S2_MCK{slash}TIM8_CH1{slash}SDIO_D6-Pad37)") (class "Default")
      (node (ref "U19") (pin "37") (pinfunction "PC6/I2S2_MCK/TIM8_CH1/SDIO_D6_37") (pintype "passive"))
    )
    (net (code "152") (name "unconnected-(U19-PC7{slash}I2S3_MCK{slash}TIM8_CH2{slash}SDIO_D7-Pad38)") (class "Default")
      (node (ref "U19") (pin "38") (pinfunction "PC7/I2S3_MCK/TIM8_CH2/SDIO_D7_38") (pintype "passive"))
    )
    (net (code "153") (name "unconnected-(U19-PC8{slash}TIM8_CH3{slash}SDIO_D0-Pad39)") (class "Default")
      (node (ref "U19") (pin "39") (pinfunction "PC8/TIM8_CH3/SDIO_D0_39") (pintype "passive"))
    )
    (net (code "154") (name "unconnected-(U19-PC9{slash}TIM8_CH4{slash}SDIO_D1-Pad40)") (class "Default")
      (node (ref "U19") (pin "40") (pinfunction "PC9/TIM8_CH4/SDIO_D1_40") (pintype "passive"))
    )
    (net (code "155") (name "unconnected-(U19-PC10{slash}U4_TX{slash}SDIO_D2-Pad51)") (class "Default")
      (node (ref "U19") (pin "51") (pinfunction "PC10/U4_TX/SDIO_D2_51") (pintype "passive"))
    )
    (net (code "156") (name "unconnected-(U19-PC11{slash}U4_RX{slash}SDIO_D3-Pad52)") (class "Default")
      (node (ref "U19") (pin "52") (pinfunction "PC11/U4_RX/SDIO_D3_52") (pintype "passive"))
    )
    (net (code "157") (name "unconnected-(U19-PC12{slash}U5_TX{slash}SDIO_CK-Pad53)") (class "Default")
      (node (ref "U19") (pin "53") (pinfunction "PC12/U5_TX/SDIO_CK_53") (pintype "passive"))
    )
    (net (code "158") (name "unconnected-(U19-PC13{slash}ANT1-Pad2)") (class "Default")
      (node (ref "U19") (pin "2") (pinfunction "PC13/ANT1_2") (pintype "passive"))
    )
    (net (code "159") (name "unconnected-(U19-PD2{slash}TIM3_ETR{slash}U5_RX{slash}SDIO_CMD-Pad54)") (class "Default")
      (node (ref "U19") (pin "54") (pinfunction "PD2/TIM3_ETR/U5_RX/SDIO_CMD_54") (pintype "passive"))
    )
  )
)
